# MOTOR_DRIVER_dupl.net
KiCad netlist of a schematic drawn in EAGLE
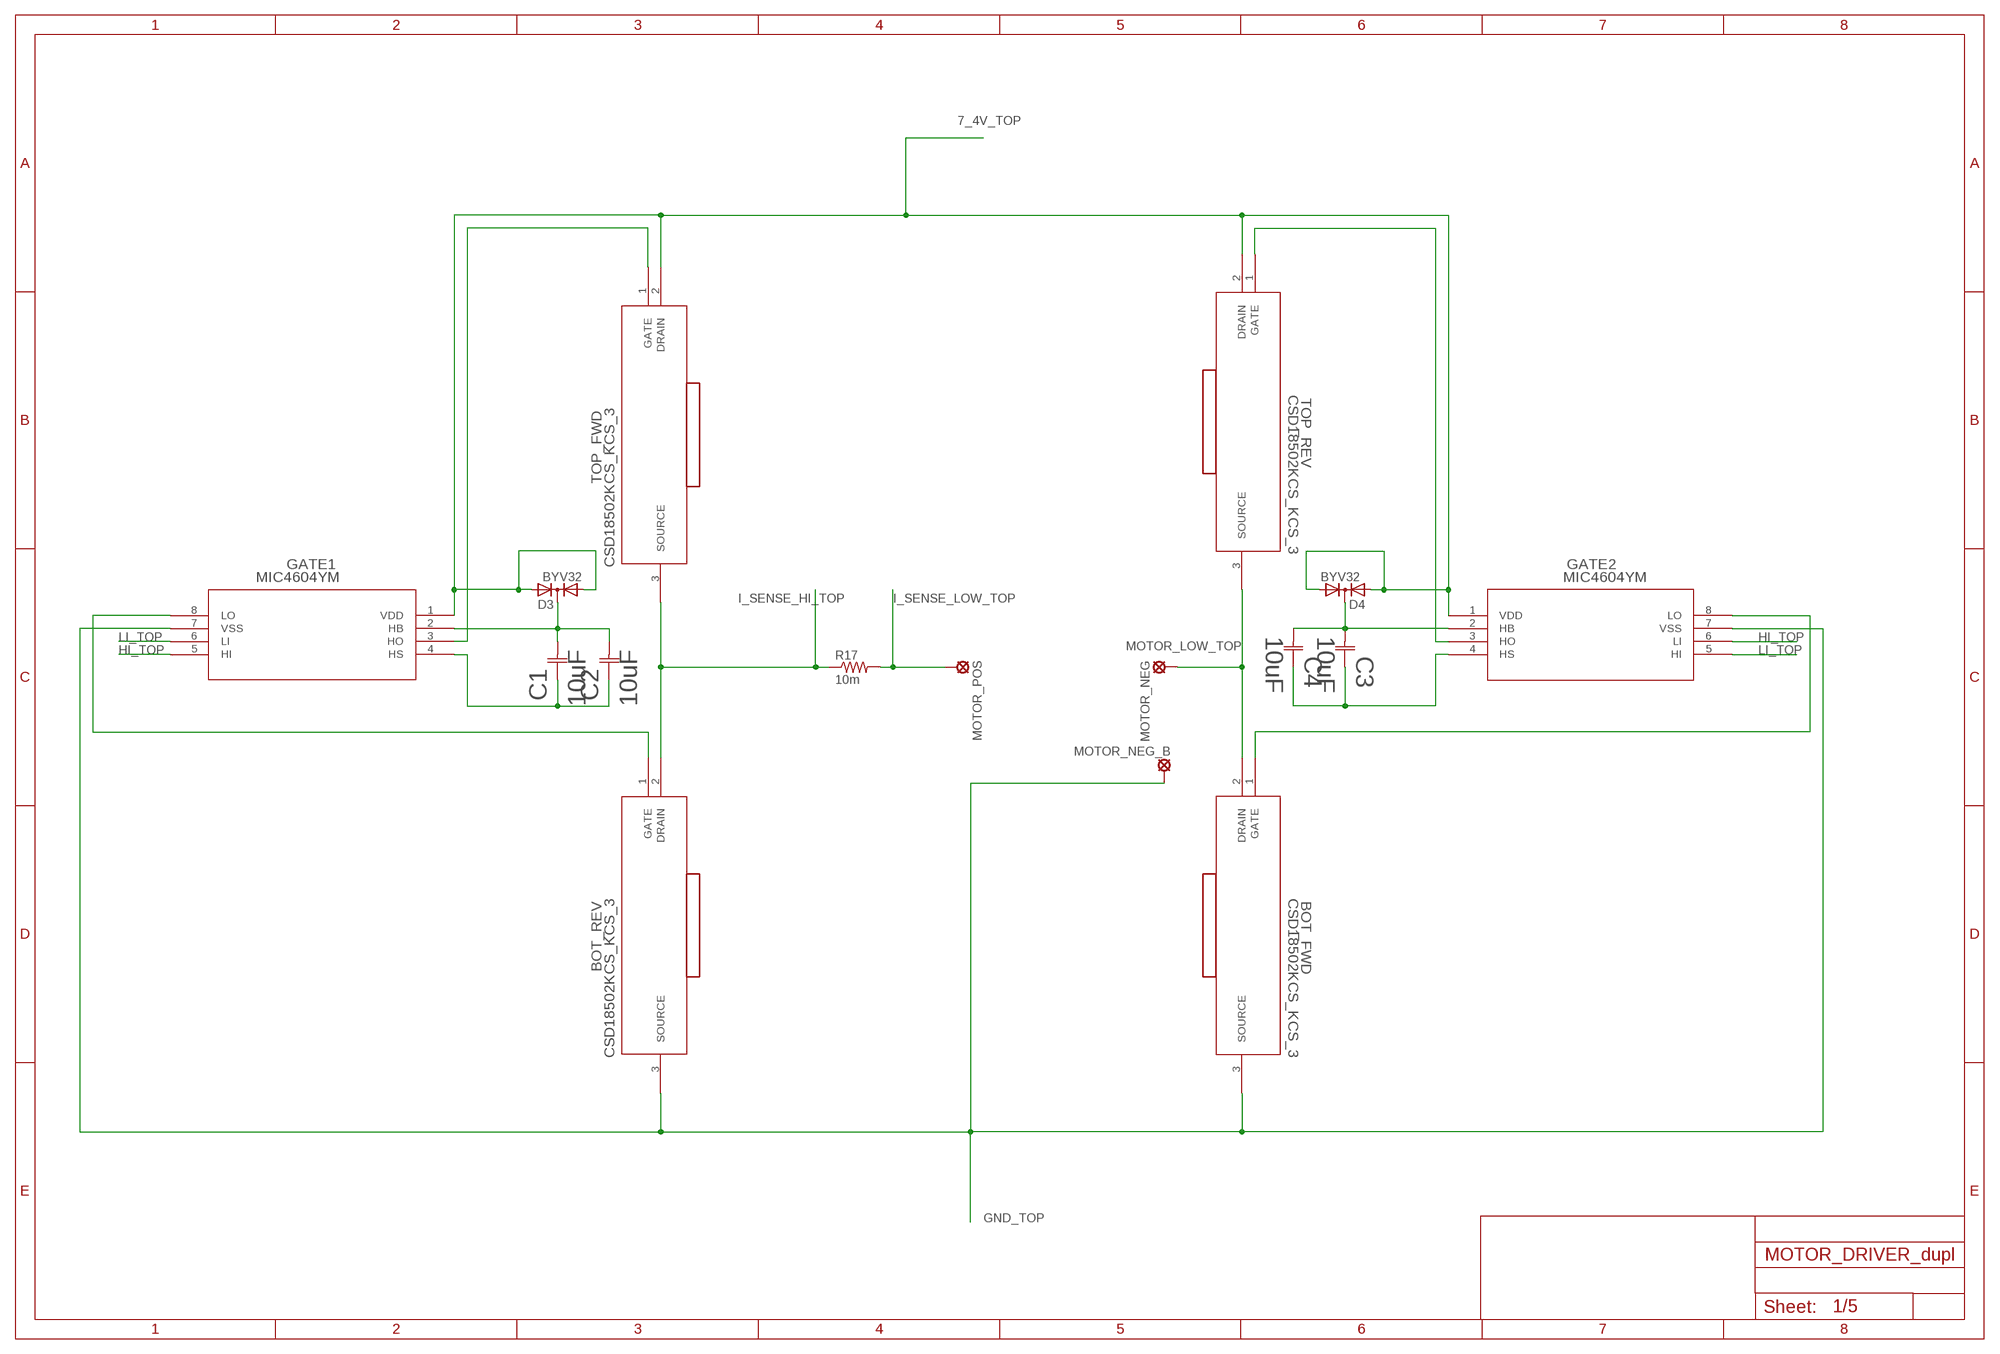
[diagram p0: schematic, sheet 1]
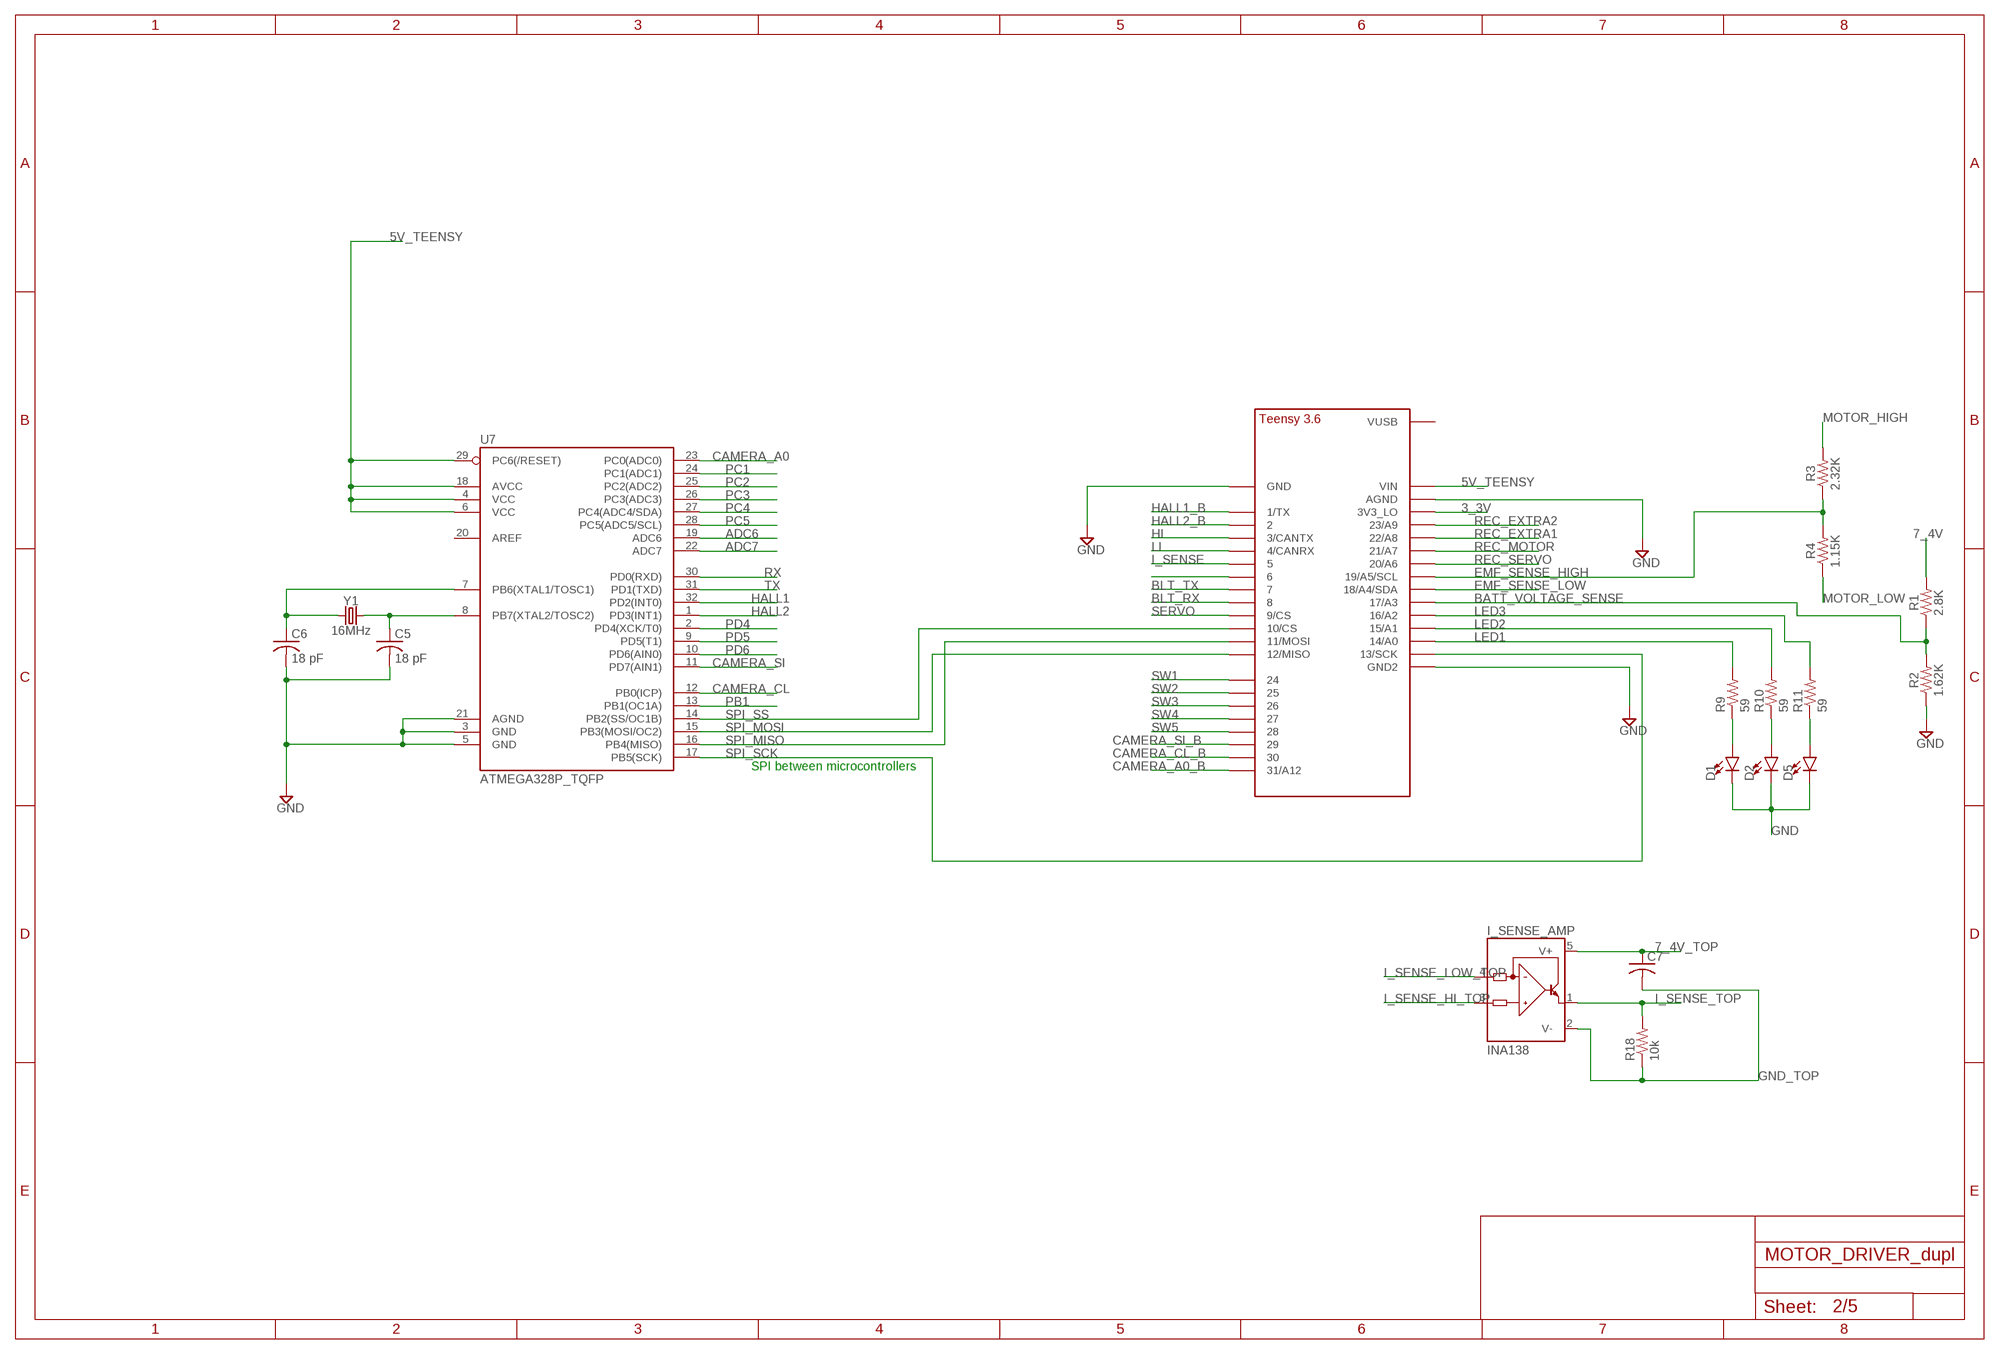
[diagram p1: schematic, sheet 2]
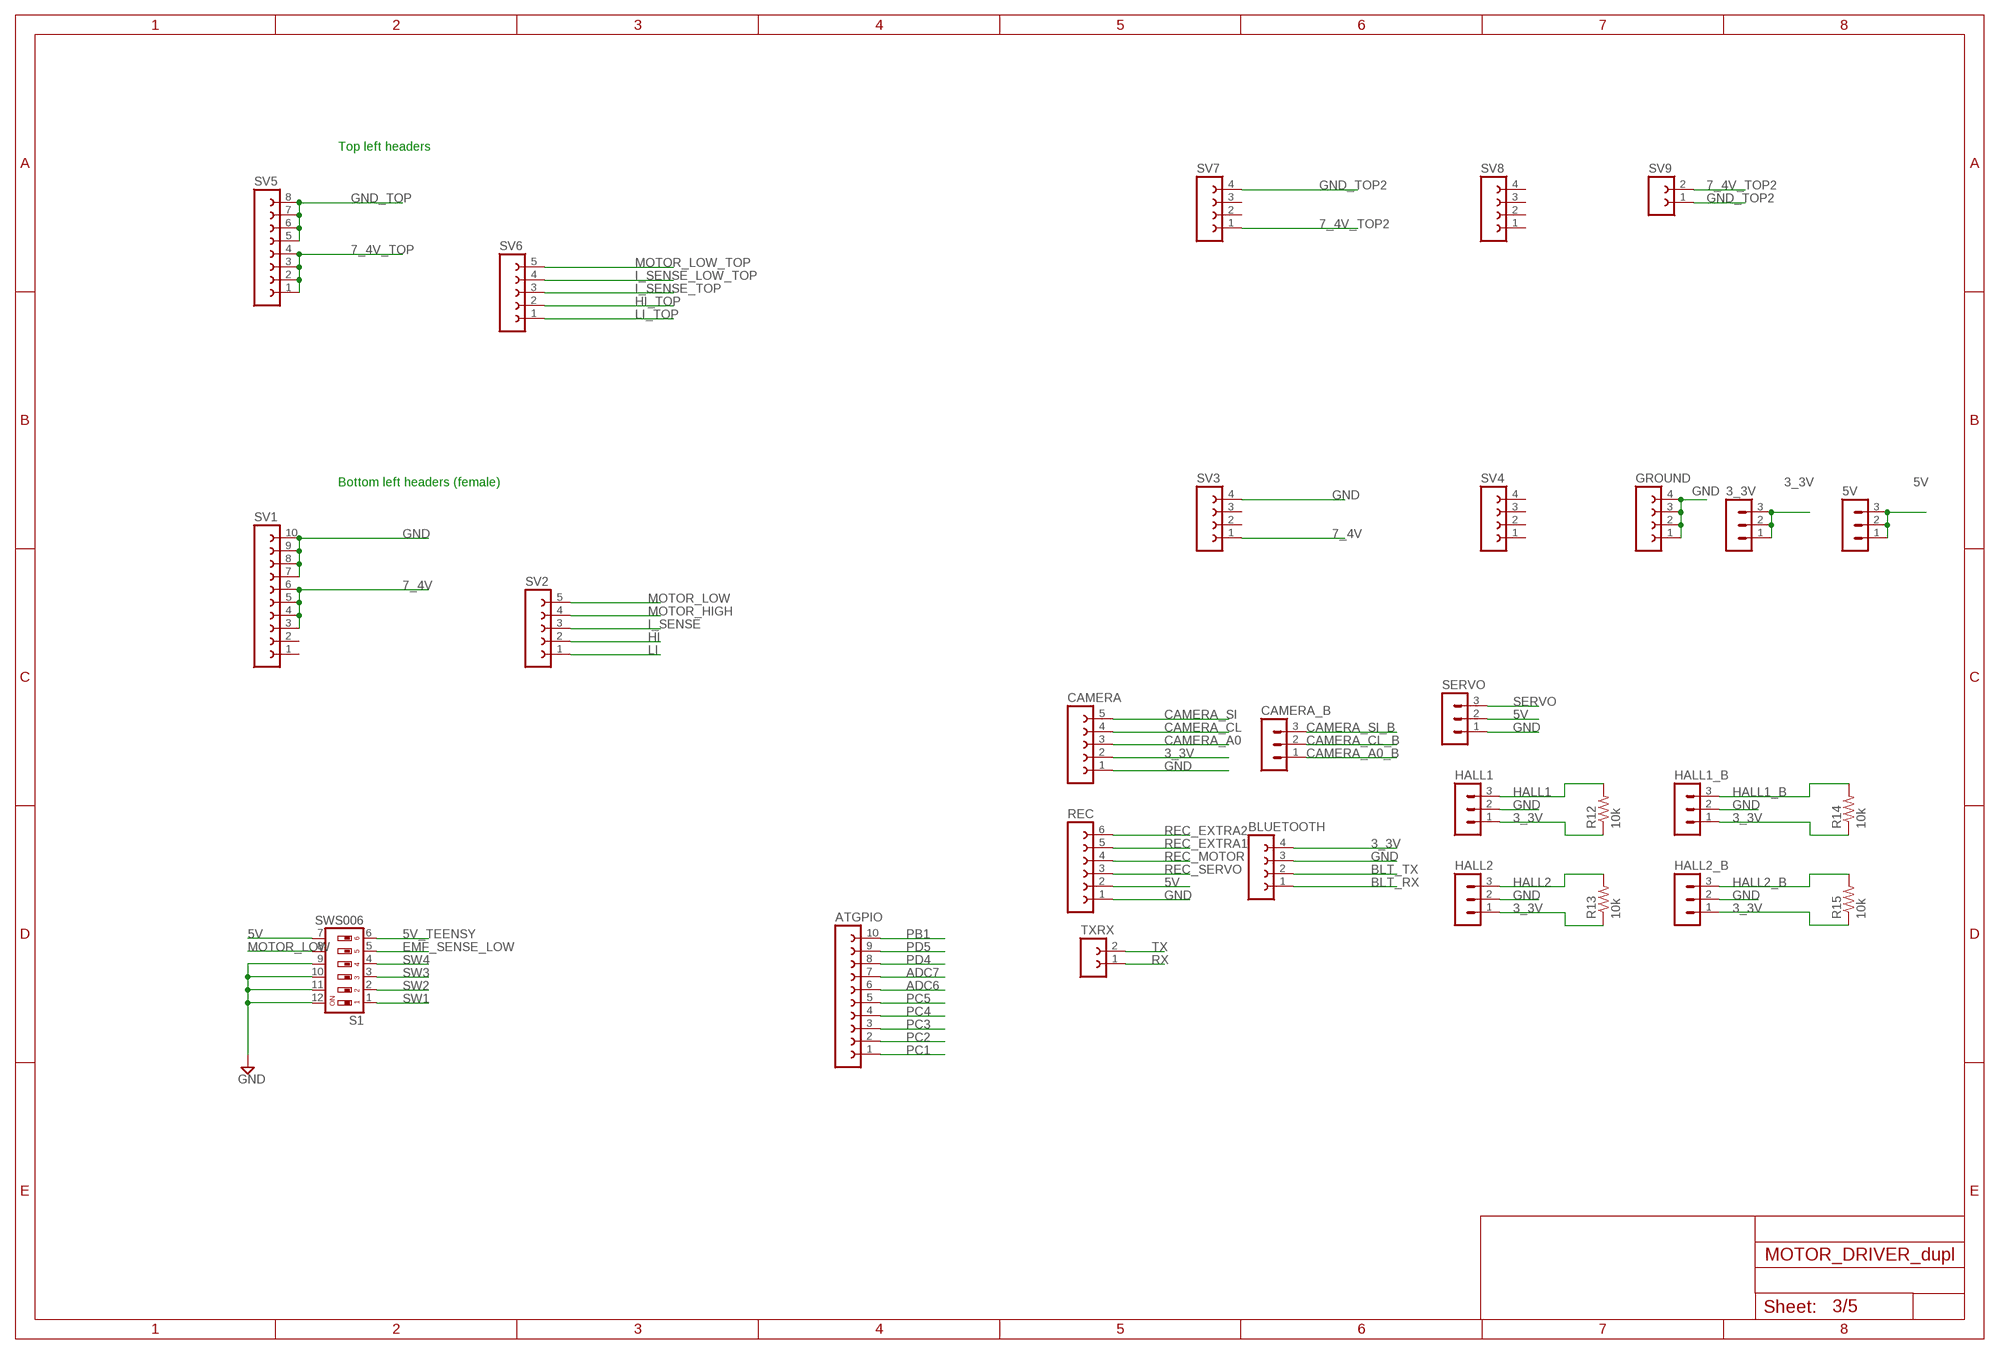
[diagram p2: schematic, sheet 3]
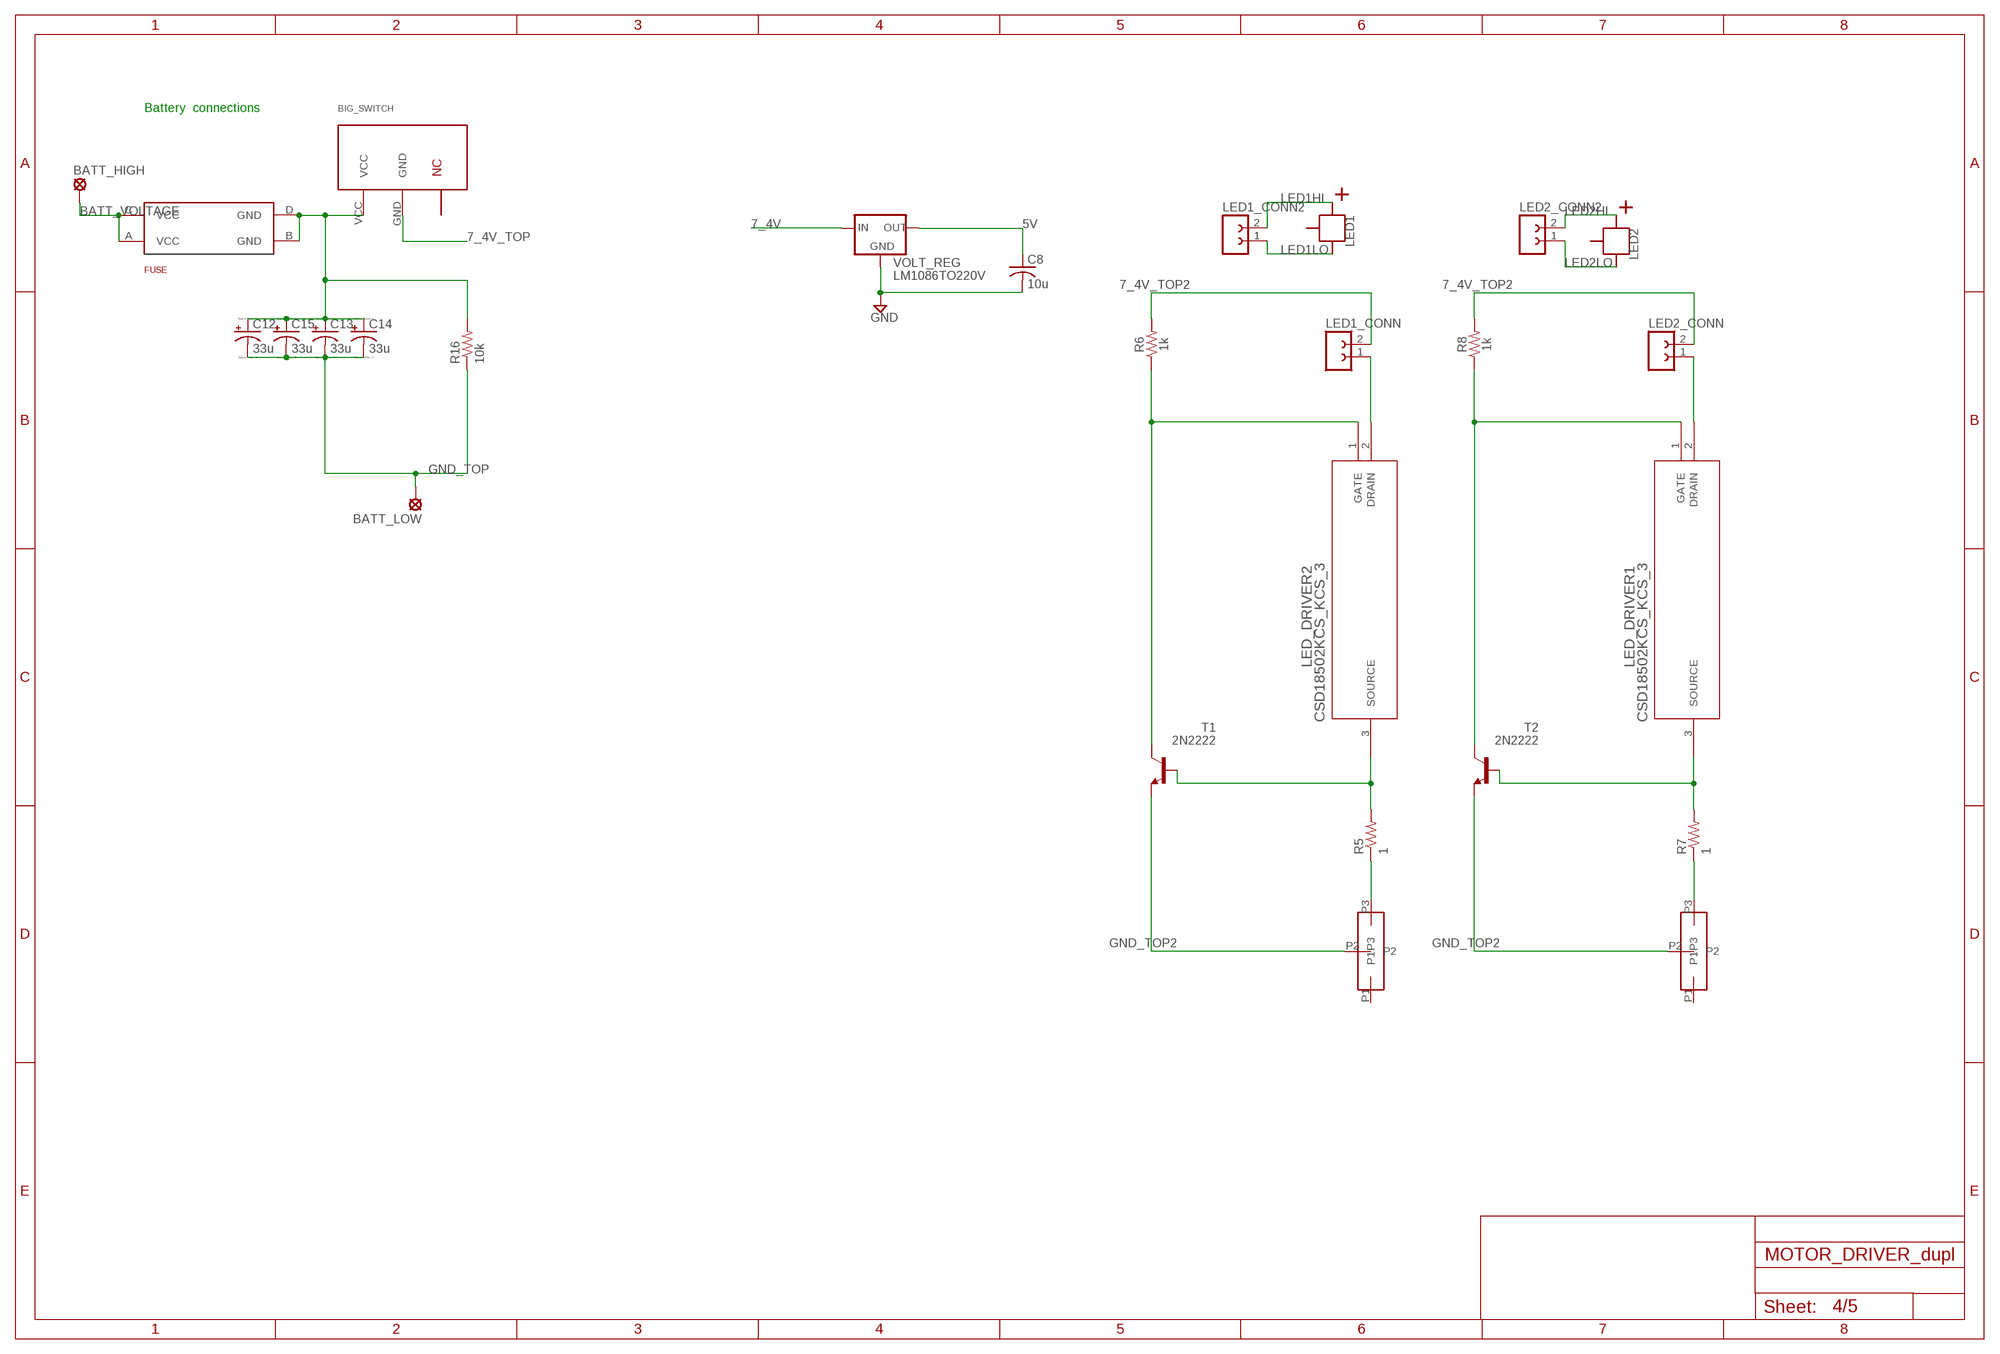
[diagram p3: schematic, sheet 4]
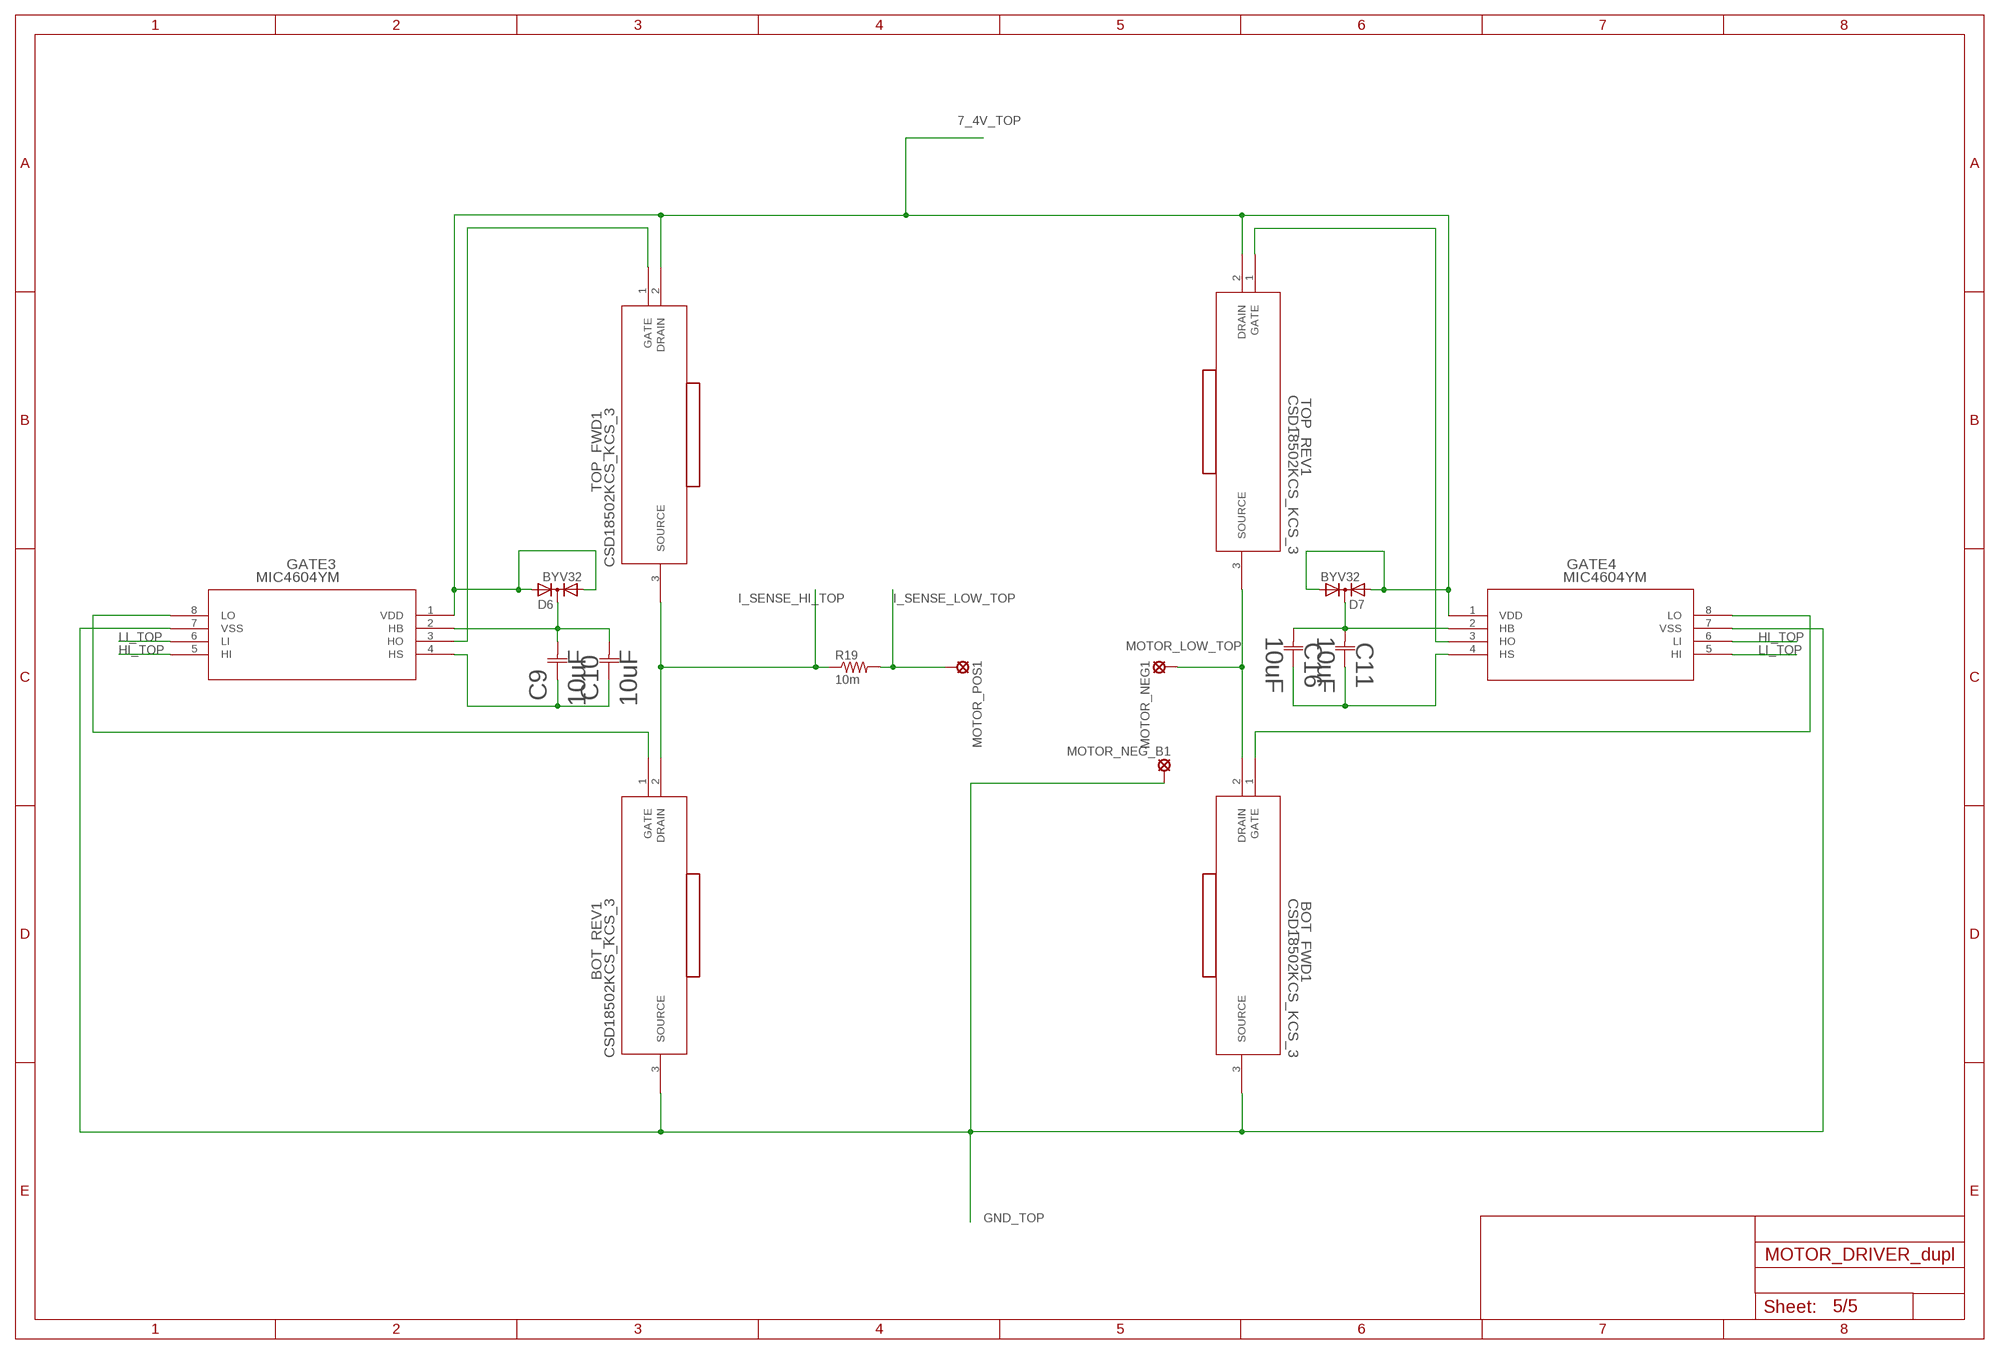
[diagram p4: schematic, sheet 5]

(export (version "E")
  (design (tool "Eeschema 10.0.6"))
  (components
    (comp (ref "C5")
      (value "18 pF")
      (footprint "eagle-import:C0603")
      (libsource (lib "eagle-import") (part "C-USC0603"))
    )
    (comp (ref "C6")
      (value "18 pF")
      (footprint "eagle-import:C0603")
      (libsource (lib "eagle-import") (part "C-USC0603"))
    )
    (comp (ref "C7")
      (value "C-USC0603")
      (footprint "eagle-import:C0603")
      (libsource (lib "eagle-import") (part "resistor_C-USC0603"))
    )
    (comp (ref "D1")
      (value "LED0603")
      (footprint "eagle-import:LED-0603")
      (libsource (lib "eagle-import") (part "LED0603"))
    )
    (comp (ref "D2")
      (value "LED0603")
      (footprint "eagle-import:LED-0603")
      (libsource (lib "eagle-import") (part "LED0603"))
    )
    (comp (ref "D5")
      (value "LED0603")
      (footprint "eagle-import:LED-0603")
      (libsource (lib "eagle-import") (part "LED0603"))
    )
    (comp (ref "I_SENSE_AMP")
      (value "INA138")
      (footprint "eagle-import:SOT23-5")
      (fields
        (field (name "DIGIKEY_PART_NUMBER") "INA138NACT-ND")
        (field (name "MANUFACTURER") "Texas Instruments")
        (field (name "MANUFACTURER_PART_NUMBER") "INA138NA/250")
      )
      (libsource (lib "eagle-import") (part "INA138"))
    )
    (comp (ref "R1")
      (value "2.8K")
      (footprint "eagle-import:0805")
      (fields
        (field (name "DIGIKEY_PART_NUMBER") "311-2.80KCRCT-ND")
        (field (name "MANUFACTURER") "Yageo")
        (field (name "MANUFACTURER_PART_NUMBER") "RC0805FR-072K8L")
      )
      (libsource (lib "eagle-import") (part "0.3OHM-0805-1/8W-1%"))
    )
    (comp (ref "R2")
      (value "1.62K")
      (footprint "eagle-import:0805")
      (fields
        (field (name "DIGIKEY_PART_NUMBER") "311-1.62KCRCT-ND")
        (field (name "MANUFACTURER") "Yageo")
        (field (name "MANUFACTURER_PART_NUMBER") "RC0805FR-071K62L")
      )
      (libsource (lib "eagle-import") (part "0.3OHM-0805-1/8W-1%"))
    )
    (comp (ref "R3")
      (value "2.32K")
      (footprint "eagle-import:0805")
      (fields
        (field (name "DIGIKEY_PART_NUMBER") "311-2.32KCRCT-ND")
        (field (name "MANUFACTURER") "Yageo")
        (field (name "MANUFACTURER_PART_NUMBER") "RC0805FR-072K32L")
      )
      (libsource (lib "eagle-import") (part "0.3OHM-0805-1/8W-1%"))
    )
    (comp (ref "R4")
      (value "1.15K")
      (footprint "eagle-import:0805")
      (fields
        (field (name "DIGIKEY_PART_NUMBER") "311-1.15KCRCT-ND")
        (field (name "MANUFACTURER") "Yageo")
        (field (name "MANUFACTURER_PART_NUMBER") "RC0805FR-071K15L")
      )
      (libsource (lib "eagle-import") (part "0.3OHM-0805-1/8W-1%"))
    )
    (comp (ref "R9")
      (value "59")
      (footprint "eagle-import:R0805")
      (libsource (lib "eagle-import") (part "R-US_R0805"))
    )
    (comp (ref "R10")
      (value "59")
      (footprint "eagle-import:R0805")
      (libsource (lib "eagle-import") (part "R-US_R0805"))
    )
    (comp (ref "R11")
      (value "59")
      (footprint "eagle-import:R0805")
      (libsource (lib "eagle-import") (part "R-US_R0805"))
    )
    (comp (ref "R18")
      (value "10k")
      (footprint "eagle-import:R0603")
      (libsource (lib "eagle-import") (part "R-US_R0603"))
    )
    (comp (ref "U$1")
      (value "TEENSY_3.5/3.6_FEWER")
      (footprint "eagle-import:TEENSY_3.5_3.6_BASIC_FEWER_PIN")
      (fields
        (field (name "DIGIKEY_PART_NUMBER") "1568-1443-ND")
        (field (name "MANUFACTURER") "SparkFun Electronics")
        (field (name "MANUFACTURER_PART_NUMBER") "DEV-14055")
      )
      (libsource (lib "eagle-import") (part "TEENSY_3.5/3.6_FEWER"))
    )
    (comp (ref "U7")
      (value "ATMEGA328P_TQFP")
      (footprint "eagle-import:TQFP32-08")
      (fields
        (field (name "DIGIKEY_PART_NUMBER") "ATMEGA328PB-AU-ND")
        (field (name "MANUFACTURER") "Microchip Technology")
        (field (name "MANUFACTURER_PART_NUMBER") "ATMEGA328PB-AU")
      )
      (libsource (lib "eagle-import") (part "ATMEGA328P_TQFP"))
    )
    (comp (ref "Y1")
      (value "16MHz")
      (footprint "eagle-import:HC49US")
      (fields
        (field (name "DIGIKEY_PART_NUMBER") "887-2425-1-ND")
        (field (name "MANUFACTURER") "TXC CORPORATION")
        (field (name "MANUFACTURER_PART_NUMBER") "9C-16.000MBBK-T")
      )
      (libsource (lib "eagle-import") (part "CRYSTAL-16MHZPTH-HC49US"))
    )
    (comp (ref "3_3V")
      (value "MA03-1")
      (footprint "eagle-import:MA03-1")
      (libsource (lib "eagle-import") (part "MA03-1"))
    )
    (comp (ref "5V")
      (value "MA03-1")
      (footprint "eagle-import:MA03-1")
      (libsource (lib "eagle-import") (part "MA03-1"))
    )
    (comp (ref "ATGPIO")
      (value "FE10-1")
      (footprint "eagle-import:FE10")
      (libsource (lib "eagle-import") (part "FE10-1"))
    )
    (comp (ref "BLUETOOTH")
      (value "FE04-1")
      (footprint "eagle-import:FE04-1")
      (fields
        (field (name "MANUFACTURER") "HC Information Technology")
        (field (name "MANUFACTURER_PART_NUMBER") "HC-06")
      )
      (libsource (lib "eagle-import") (part "FE04-1"))
    )
    (comp (ref "CAMERA")
      (value "FE05-1")
      (footprint "eagle-import:FE05-1")
      (fields
        (field (name "DIGIKEY_PART_NUMBER") "28317-ND")
        (field (name "MANUFACTURER") "Parallax")
        (field (name "MANUFACTURER_PART_NUMBER") "28317")
      )
      (libsource (lib "eagle-import") (part "FE05-1"))
    )
    (comp (ref "CAMERA_B")
      (value "MA03-1")
      (footprint "eagle-import:MA03-1")
      (fields
        (field (name "DIGIKEY_PART_NUMBER") "28317-ND")
        (field (name "MANUFACTURER") "Parallax")
        (field (name "MANUFACTURER_PART_NUMBER") "28317")
      )
      (libsource (lib "eagle-import") (part "MA03-1"))
    )
    (comp (ref "GROUND")
      (value "FE04-1")
      (footprint "eagle-import:FE04-1")
      (libsource (lib "eagle-import") (part "FE04-1"))
    )
    (comp (ref "HALL1")
      (value "MA03-1")
      (footprint "eagle-import:MA03-1")
      (fields
        (field (name "DIGIKEY_PART_NUMBER") "US1881LUA-AAA-000-BU-ND")
        (field (name "MANUFACTURER") "Melexis Technologies NV")
        (field (name "MANUFACTURER_PART_NUMBER") "US1881LUA-AAA-000-BU")
      )
      (libsource (lib "eagle-import") (part "MA03-1"))
    )
    (comp (ref "HALL1_B")
      (value "MA03-1")
      (footprint "eagle-import:MA03-1")
      (fields
        (field (name "DIGIKEY_PART_NUMBER") "US1881LUA-AAA-000-BU-ND")
        (field (name "MANUFACTURER") "Melexis Technologies NV")
        (field (name "MANUFACTURER_PART_NUMBER") "US1881LUA-AAA-000-BU")
      )
      (libsource (lib "eagle-import") (part "MA03-1"))
    )
    (comp (ref "HALL2")
      (value "MA03-1")
      (footprint "eagle-import:MA03-1")
      (fields
        (field (name "DIGIKEY_PART_NUMBER") "US1881LUA-AAA-000-BU-ND")
        (field (name "MANUFACTURER") "Melexis Technologies NV")
        (field (name "MANUFACTURER_PART_NUMBER") "US1881LUA-AAA-000-BU")
      )
      (libsource (lib "eagle-import") (part "MA03-1"))
    )
    (comp (ref "HALL2_B")
      (value "MA03-1")
      (footprint "eagle-import:MA03-1")
      (fields
        (field (name "DIGIKEY_PART_NUMBER") "US1881LUA-AAA-000-BU-ND")
        (field (name "MANUFACTURER") "Melexis Technologies NV")
        (field (name "MANUFACTURER_PART_NUMBER") "US1881LUA-AAA-000-BU")
      )
      (libsource (lib "eagle-import") (part "MA03-1"))
    )
    (comp (ref "R12")
      (value "10k")
      (footprint "eagle-import:R0603")
      (libsource (lib "eagle-import") (part "resistor_R-US_R0603"))
    )
    (comp (ref "R13")
      (value "10k")
      (footprint "eagle-import:R0603")
      (libsource (lib "eagle-import") (part "resistor_R-US_R0603"))
    )
    (comp (ref "R14")
      (value "10k")
      (footprint "eagle-import:R0603")
      (libsource (lib "eagle-import") (part "resistor_R-US_R0603"))
    )
    (comp (ref "R15")
      (value "10k")
      (footprint "eagle-import:R0603")
      (libsource (lib "eagle-import") (part "resistor_R-US_R0603"))
    )
    (comp (ref "REC")
      (value "FE06-1")
      (footprint "eagle-import:FE06")
      (libsource (lib "eagle-import") (part "FE06-1"))
    )
    (comp (ref "S1")
      (value "SWS006")
      (footprint "eagle-import:SMS-006")
      (fields
        (field (name "DIGIKEY_PART_NUMBER") "CT2196MST-ND")
        (field (name "MANUFACTURER") "CTS Electrocomponents")
        (field (name "MANUFACTURER_PART_NUMBER") "219-6MST")
      )
      (libsource (lib "eagle-import") (part "SWS006"))
    )
    (comp (ref "SERVO")
      (value "MA03-1")
      (footprint "eagle-import:MA03-1")
      (fields (field (name "MANUFACTURER") "TrackStar") (field (name "MANUFACTURER_PART_NUMBER") "TS-P12S"))
      (libsource (lib "eagle-import") (part "MA03-1"))
    )
    (comp (ref "SV1")
      (value "FE10-1")
      (footprint "eagle-import:FE10")
      (libsource (lib "eagle-import") (part "FE10-1"))
    )
    (comp (ref "SV2")
      (value "FE05-1")
      (footprint "eagle-import:FE05-1")
      (libsource (lib "eagle-import") (part "FE05-1"))
    )
    (comp (ref "SV3")
      (value "FE04-1")
      (footprint "eagle-import:FE04-1")
      (libsource (lib "eagle-import") (part "FE04-1"))
    )
    (comp (ref "SV4")
      (value "FE04-1")
      (footprint "eagle-import:FE04-1")
      (libsource (lib "eagle-import") (part "FE04-1"))
    )
    (comp (ref "SV5")
      (value "FE08-1")
      (footprint "eagle-import:FE08")
      (libsource (lib "eagle-import") (part "FE08-1"))
    )
    (comp (ref "SV6")
      (value "FE05-1")
      (footprint "eagle-import:FE05-1")
      (libsource (lib "eagle-import") (part "FE05-1"))
    )
    (comp (ref "SV7")
      (value "FE04-1")
      (footprint "eagle-import:FE04-1")
      (libsource (lib "eagle-import") (part "FE04-1"))
    )
    (comp (ref "SV8")
      (value "FE04-1")
      (footprint "eagle-import:FE04-1")
      (libsource (lib "eagle-import") (part "FE04-1"))
    )
    (comp (ref "SV9")
      (value "FE02-1")
      (footprint "eagle-import:FE02-1")
      (libsource (lib "eagle-import") (part "FE02-1"))
    )
    (comp (ref "TXRX")
      (value "FE02-1")
      (footprint "eagle-import:FE02-1")
      (libsource (lib "eagle-import") (part "FE02-1"))
    )
    (comp (ref "BOT_FWD")
      (value "CSD18502KCS_KCS_3")
      (footprint "eagle-import:KCS3")
      (fields
        (field (name "DIGIKEY_PART_NUMBER") "296-35013-ND")
        (field (name "MANUFACTURER") "Texas Instruments")
        (field (name "MANUFACTURER_PART_NUMBER") "CSD18533KCS")
      )
      (libsource (lib "eagle-import") (part "CSD18502KCS_KCS_3"))
    )
    (comp (ref "BOT_REV")
      (value "CSD18502KCS_KCS_3")
      (footprint "eagle-import:KCS3")
      (fields
        (field (name "DIGIKEY_PART_NUMBER") "296-35013-ND")
        (field (name "MANUFACTURER") "Texas Instruments")
        (field (name "MANUFACTURER_PART_NUMBER") "CSD18533KCS")
      )
      (libsource (lib "eagle-import") (part "CSD18502KCS_KCS_3"))
    )
    (comp (ref "C1")
      (value "10uF")
      (footprint "eagle-import:CAP_EEE_B")
      (fields (field (name "MANUFACTURER_PART_NUMBER") "EEE1VA100WR"))
      (libsource (lib "eagle-import") (part "EEE1VA100WR"))
    )
    (comp (ref "C2")
      (value "10uF")
      (footprint "eagle-import:CAP_EEE_B")
      (fields (field (name "MANUFACTURER_PART_NUMBER") "EEE1VA100WR"))
      (libsource (lib "eagle-import") (part "EEE1VA100WR"))
    )
    (comp (ref "C3")
      (value "10uF")
      (footprint "eagle-import:CAP_EEE_B")
      (fields (field (name "MANUFACTURER_PART_NUMBER") "EEE1VA100WR"))
      (libsource (lib "eagle-import") (part "EEE1VA100WR"))
    )
    (comp (ref "C4")
      (value "10uF")
      (footprint "eagle-import:CAP_EEE_B")
      (fields (field (name "MANUFACTURER_PART_NUMBER") "EEE1VA100WR"))
      (libsource (lib "eagle-import") (part "EEE1VA100WR"))
    )
    (comp (ref "D3")
      (value "BYV32")
      (footprint "eagle-import:TO220ABS")
      (libsource (lib "eagle-import") (part "BYV32"))
    )
    (comp (ref "D4")
      (value "BYV32")
      (footprint "eagle-import:TO220ABS")
      (libsource (lib "eagle-import") (part "BYV32"))
    )
    (comp (ref "GATE1")
      (value "MIC4604YM")
      (footprint "eagle-import:SOIC-8_M")
      (fields
        (field (name "DIGIKEY_PART_NUMBER") "576-4395-1-ND")
        (field (name "MANUFACTURER") "Microchip")
        (field (name "MANUFACTURER_PART_NUMBER") "MIC4604YM-T5")
      )
      (libsource (lib "eagle-import") (part "MIC4604YM"))
    )
    (comp (ref "GATE2")
      (value "MIC4604YM")
      (footprint "eagle-import:SOIC-8_M")
      (fields
        (field (name "DIGIKEY_PART_NUMBER") "576-4395-1-ND")
        (field (name "MANUFACTURER") "Microchip")
        (field (name "MANUFACTURER_PART_NUMBER") "MIC4604YM-T5")
      )
      (libsource (lib "eagle-import") (part "MIC4604YM"))
    )
    (comp (ref "MOTOR_NEG")
      (value "SE14")
      (footprint "eagle-import:SE14")
      (libsource (lib "eagle-import") (part "SE14"))
    )
    (comp (ref "MOTOR_NEG_B")
      (value "SE14")
      (footprint "eagle-import:SE14")
      (libsource (lib "eagle-import") (part "SE14"))
    )
    (comp (ref "MOTOR_POS")
      (value "SE14")
      (footprint "eagle-import:SE14")
      (libsource (lib "eagle-import") (part "SE14"))
    )
    (comp (ref "R17")
      (value "10m")
      (footprint "eagle-import:R2512")
      (libsource (lib "eagle-import") (part "R-US_R2512"))
    )
    (comp (ref "TOP_FWD")
      (value "CSD18502KCS_KCS_3")
      (footprint "eagle-import:KCS3")
      (fields
        (field (name "DIGIKEY_PART_NUMBER") "296-35013-ND")
        (field (name "MANUFACTURER") "Texas Instruments")
        (field (name "MANUFACTURER_PART_NUMBER") "CSD18533KCS")
      )
      (libsource (lib "eagle-import") (part "CSD18502KCS_KCS_3"))
    )
    (comp (ref "TOP_REV")
      (value "CSD18502KCS_KCS_3")
      (footprint "eagle-import:KCS3")
      (fields
        (field (name "DIGIKEY_PART_NUMBER") "296-35013-ND")
        (field (name "MANUFACTURER") "Texas Instruments")
        (field (name "MANUFACTURER_PART_NUMBER") "CSD18533KCS")
      )
      (libsource (lib "eagle-import") (part "CSD18502KCS_KCS_3"))
    )
    (comp (ref "U$2")
      (value "HEATSINK")
      (footprint "eagle-import:HEATSINK")
      (fields
        (field (name "DIGIKEY_PART_NUMBER") "HS112-ND")
        (field (name "MANUFACTURER") "Aavid Thermalloy")
        (field (name "MANUFACTURER_PART_NUMBER") "507002B00000G")
      )
      (libsource (lib "eagle-import") (part "HEATSINK"))
    )
    (comp (ref "U$4")
      (value "HEATSINK")
      (footprint "eagle-import:HEATSINK")
      (fields
        (field (name "DIGIKEY_PART_NUMBER") "HS112-ND")
        (field (name "MANUFACTURER") "Aavid Thermalloy")
        (field (name "MANUFACTURER_PART_NUMBER") "507002B00000G")
      )
      (libsource (lib "eagle-import") (part "HEATSINK"))
    )
    (comp (ref "U$5")
      (value "HEATSINK")
      (footprint "eagle-import:HEATSINK")
      (fields
        (field (name "DIGIKEY_PART_NUMBER") "HS112-ND")
        (field (name "MANUFACTURER") "Aavid Thermalloy")
        (field (name "MANUFACTURER_PART_NUMBER") "507002B00000G")
      )
      (libsource (lib "eagle-import") (part "HEATSINK"))
    )
    (comp (ref "U$6")
      (value "HEATSINK")
      (footprint "eagle-import:HEATSINK")
      (fields
        (field (name "DIGIKEY_PART_NUMBER") "HS112-ND")
        (field (name "MANUFACTURER") "Aavid Thermalloy")
        (field (name "MANUFACTURER_PART_NUMBER") "507002B00000G")
      )
      (libsource (lib "eagle-import") (part "HEATSINK"))
    )
    (comp (ref "BATT_HIGH")
      (value "SE14")
      (footprint "eagle-import:SE14")
      (libsource (lib "eagle-import") (part "SE14"))
    )
    (comp (ref "BATT_LOW")
      (value "SE14")
      (footprint "eagle-import:SE14")
      (libsource (lib "eagle-import") (part "SE14"))
    )
    (comp (ref "BIG_SWITCH")
      (value "BIGSWITCH")
      (footprint "eagle-import:BIGSWITCH")
      (fields
        (field (name "DIGIKEY_PART_NUMBER") "CW106-ND")
        (field (name "MANUFACTURER") "CW Industries")
        (field (name "MANUFACTURER_PART_NUMBER") "GRB238B801BR1")
      )
      (libsource (lib "eagle-import") (part "BIGSWITCH"))
    )
    (comp (ref "C8")
      (value "10u")
      (footprint "eagle-import:C0805")
      (libsource (lib "eagle-import") (part "C-USC0805"))
    )
    (comp (ref "C12")
      (value "33u")
      (footprint "eagle-import:153CLV-1010")
      (libsource (lib "eagle-import") (part "CPOL-US153CLV-1010"))
    )
    (comp (ref "C13")
      (value "33u")
      (footprint "eagle-import:153CLV-1010")
      (libsource (lib "eagle-import") (part "CPOL-US153CLV-1010"))
    )
    (comp (ref "C14")
      (value "33u")
      (footprint "eagle-import:153CLV-1010")
      (libsource (lib "eagle-import") (part "CPOL-US153CLV-1010"))
    )
    (comp (ref "C15")
      (value "33u")
      (footprint "eagle-import:153CLV-1010")
      (libsource (lib "eagle-import") (part "CPOL-US153CLV-1010"))
    )
    (comp (ref "FUSE")
      (value "FUSEHOLDER3588")
      (footprint "eagle-import:FUSEHOLDER3588")
      (fields
        (field (name "DIGIKEY_PART_NUMBER") "F4989-ND")
        (field (name "MANUFACTURER") "Littelfuse Inc.")
        (field (name "MANUFACTURER_PART_NUMBER") "0891010.NXS")
      )
      (libsource (lib "eagle-import") (part "FUSEHOLDER3588"))
    )
    (comp (ref "LED1")
      (value "CREE_XP")
      (footprint "eagle-import:XP")
      (libsource (lib "eagle-import") (part "CREE_XP"))
    )
    (comp (ref "LED1_CONN")
      (value "FE02-1")
      (footprint "eagle-import:FE02-1")
      (libsource (lib "eagle-import") (part "FE02-1"))
    )
    (comp (ref "LED1_CONN2")
      (value "FE02-1")
      (footprint "eagle-import:FE02-1")
      (libsource (lib "eagle-import") (part "FE02-1"))
    )
    (comp (ref "LED2")
      (value "CREE_XP")
      (footprint "eagle-import:XP")
      (libsource (lib "eagle-import") (part "CREE_XP"))
    )
    (comp (ref "LED2_CONN")
      (value "FE02-1")
      (footprint "eagle-import:FE02-1")
      (libsource (lib "eagle-import") (part "FE02-1"))
    )
    (comp (ref "LED2_CONN2")
      (value "FE02-1")
      (footprint "eagle-import:FE02-1")
      (libsource (lib "eagle-import") (part "FE02-1"))
    )
    (comp (ref "LED_DRIVER1")
      (value "CSD18502KCS_KCS_3")
      (footprint "eagle-import:KCS3")
      (fields
        (field (name "DIGIKEY_PART_NUMBER") "296-35013-ND")
        (field (name "MANUFACTURER") "Texas Instruments")
        (field (name "MANUFACTURER_PART_NUMBER") "CSD18533KCS")
      )
      (libsource (lib "eagle-import") (part "CSD18502KCS_KCS_3"))
    )
    (comp (ref "LED_DRIVER2")
      (value "CSD18502KCS_KCS_3")
      (footprint "eagle-import:KCS3")
      (fields
        (field (name "DIGIKEY_PART_NUMBER") "296-35013-ND")
        (field (name "MANUFACTURER") "Texas Instruments")
        (field (name "MANUFACTURER_PART_NUMBER") "CSD18533KCS")
      )
      (libsource (lib "eagle-import") (part "CSD18502KCS_KCS_3"))
    )
    (comp (ref "R5")
      (value "1")
      (footprint "eagle-import:R2512")
      (libsource (lib "eagle-import") (part "R-US_R2512"))
    )
    (comp (ref "R6")
      (value "1k")
      (footprint "eagle-import:AXIAL-0.3")
      (libsource (lib "eagle-import") (part "1KOHM-HORIZ-1/4W-1%"))
    )
    (comp (ref "R7")
      (value "1")
      (footprint "eagle-import:R2512")
      (libsource (lib "eagle-import") (part "R-US_R2512"))
    )
    (comp (ref "R8")
      (value "1k")
      (footprint "eagle-import:AXIAL-0.3")
      (libsource (lib "eagle-import") (part "1KOHM-HORIZ-1/4W-1%"))
    )
    (comp (ref "R16")
      (value "10k")
      (footprint "eagle-import:R0603")
      (libsource (lib "eagle-import") (part "resistor_R-US_R0603"))
    )
    (comp (ref "T1")
      (value "2N2222")
      (footprint "eagle-import:TO18")
      (libsource (lib "eagle-import") (part "2N2222"))
    )
    (comp (ref "T2")
      (value "2N2222")
      (footprint "eagle-import:TO18")
      (libsource (lib "eagle-import") (part "2N2222"))
    )
    (comp (ref "U$3")
      (value "POT")
      (footprint "eagle-import:POT")
      (libsource (lib "eagle-import") (part "POT"))
    )
    (comp (ref "U$7")
      (value "POT")
      (footprint "eagle-import:POT")
      (libsource (lib "eagle-import") (part "POT"))
    )
    (comp (ref "VOLT_REG")
      (value "LM1086TO220V")
      (footprint "eagle-import:TO220S")
      (fields
        (field (name "DIGIKEY_PART_NUMBER") "LM1086IT-5.0/NOPB-ND")
        (field (name "MANUFACTURER") "Texas Instruments")
        (field (name "MANUFACTURER_PART_NUMBER") "LM1086IT-5.0/NOPB")
      )
      (libsource (lib "eagle-import") (part "LM1086TO220V"))
    )
    (comp (ref "BOT_FWD1")
      (value "CSD18502KCS_KCS_3")
      (footprint "eagle-import:KCS3")
      (fields
        (field (name "DIGIKEY_PART_NUMBER") "296-35013-ND")
        (field (name "MANUFACTURER") "Texas Instruments")
        (field (name "MANUFACTURER_PART_NUMBER") "CSD18533KCS")
      )
      (libsource (lib "eagle-import") (part "CSD18502KCS_KCS_3"))
    )
    (comp (ref "BOT_REV1")
      (value "CSD18502KCS_KCS_3")
      (footprint "eagle-import:KCS3")
      (fields
        (field (name "DIGIKEY_PART_NUMBER") "296-35013-ND")
        (field (name "MANUFACTURER") "Texas Instruments")
        (field (name "MANUFACTURER_PART_NUMBER") "CSD18533KCS")
      )
      (libsource (lib "eagle-import") (part "CSD18502KCS_KCS_3"))
    )
    (comp (ref "C9")
      (value "10uF")
      (footprint "eagle-import:CAP_EEE_B")
      (fields (field (name "MANUFACTURER_PART_NUMBER") "EEE1VA100WR"))
      (libsource (lib "eagle-import") (part "EEE1VA100WR"))
    )
    (comp (ref "C10")
      (value "10uF")
      (footprint "eagle-import:CAP_EEE_B")
      (fields (field (name "MANUFACTURER_PART_NUMBER") "EEE1VA100WR"))
      (libsource (lib "eagle-import") (part "EEE1VA100WR"))
    )
    (comp (ref "C11")
      (value "10uF")
      (footprint "eagle-import:CAP_EEE_B")
      (fields (field (name "MANUFACTURER_PART_NUMBER") "EEE1VA100WR"))
      (libsource (lib "eagle-import") (part "EEE1VA100WR"))
    )
    (comp (ref "C16")
      (value "10uF")
      (footprint "eagle-import:CAP_EEE_B")
      (fields (field (name "MANUFACTURER_PART_NUMBER") "EEE1VA100WR"))
      (libsource (lib "eagle-import") (part "EEE1VA100WR"))
    )
    (comp (ref "D6")
      (value "BYV32")
      (footprint "eagle-import:TO220ABS")
      (libsource (lib "eagle-import") (part "BYV32"))
    )
    (comp (ref "D7")
      (value "BYV32")
      (footprint "eagle-import:TO220ABS")
      (libsource (lib "eagle-import") (part "BYV32"))
    )
    (comp (ref "GATE3")
      (value "MIC4604YM")
      (footprint "eagle-import:SOIC-8_M")
      (fields
        (field (name "DIGIKEY_PART_NUMBER") "576-4395-1-ND")
        (field (name "MANUFACTURER") "Microchip")
        (field (name "MANUFACTURER_PART_NUMBER") "MIC4604YM-T5")
      )
      (libsource (lib "eagle-import") (part "MIC4604YM"))
    )
    (comp (ref "GATE4")
      (value "MIC4604YM")
      (footprint "eagle-import:SOIC-8_M")
      (fields
        (field (name "DIGIKEY_PART_NUMBER") "576-4395-1-ND")
        (field (name "MANUFACTURER") "Microchip")
        (field (name "MANUFACTURER_PART_NUMBER") "MIC4604YM-T5")
      )
      (libsource (lib "eagle-import") (part "MIC4604YM"))
    )
    (comp (ref "MOTOR_NEG1")
      (value "SE14")
      (footprint "eagle-import:SE14")
      (libsource (lib "eagle-import") (part "SE14"))
    )
    (comp (ref "MOTOR_NEG_B1")
      (value "SE14")
      (footprint "eagle-import:SE14")
      (libsource (lib "eagle-import") (part "SE14"))
    )
    (comp (ref "MOTOR_POS1")
      (value "SE14")
      (footprint "eagle-import:SE14")
      (libsource (lib "eagle-import") (part "SE14"))
    )
    (comp (ref "R19")
      (value "10m")
      (footprint "eagle-import:R2512")
      (libsource (lib "eagle-import") (part "R-US_R2512"))
    )
    (comp (ref "TOP_FWD1")
      (value "CSD18502KCS_KCS_3")
      (footprint "eagle-import:KCS3")
      (fields
        (field (name "DIGIKEY_PART_NUMBER") "296-35013-ND")
        (field (name "MANUFACTURER") "Texas Instruments")
        (field (name "MANUFACTURER_PART_NUMBER") "CSD18533KCS")
      )
      (libsource (lib "eagle-import") (part "CSD18502KCS_KCS_3"))
    )
    (comp (ref "TOP_REV1")
      (value "CSD18502KCS_KCS_3")
      (footprint "eagle-import:KCS3")
      (fields
        (field (name "DIGIKEY_PART_NUMBER") "296-35013-ND")
        (field (name "MANUFACTURER") "Texas Instruments")
        (field (name "MANUFACTURER_PART_NUMBER") "CSD18533KCS")
      )
      (libsource (lib "eagle-import") (part "CSD18502KCS_KCS_3"))
    )
    (comp (ref "U$9")
      (value "HEATSINK")
      (footprint "eagle-import:HEATSINK")
      (fields
        (field (name "DIGIKEY_PART_NUMBER") "HS112-ND")
        (field (name "MANUFACTURER") "Aavid Thermalloy")
        (field (name "MANUFACTURER_PART_NUMBER") "507002B00000G")
      )
      (libsource (lib "eagle-import") (part "HEATSINK"))
    )
    (comp (ref "U$10")
      (value "HEATSINK")
      (footprint "eagle-import:HEATSINK")
      (fields
        (field (name "DIGIKEY_PART_NUMBER") "HS112-ND")
        (field (name "MANUFACTURER") "Aavid Thermalloy")
        (field (name "MANUFACTURER_PART_NUMBER") "507002B00000G")
      )
      (libsource (lib "eagle-import") (part "HEATSINK"))
    )
    (comp (ref "U$11")
      (value "HEATSINK")
      (footprint "eagle-import:HEATSINK")
      (fields
        (field (name "DIGIKEY_PART_NUMBER") "HS112-ND")
        (field (name "MANUFACTURER") "Aavid Thermalloy")
        (field (name "MANUFACTURER_PART_NUMBER") "507002B00000G")
      )
      (libsource (lib "eagle-import") (part "HEATSINK"))
    )
    (comp (ref "U$12")
      (value "HEATSINK")
      (footprint "eagle-import:HEATSINK")
      (fields
        (field (name "DIGIKEY_PART_NUMBER") "HS112-ND")
        (field (name "MANUFACTURER") "Aavid Thermalloy")
        (field (name "MANUFACTURER_PART_NUMBER") "507002B00000G")
      )
      (libsource (lib "eagle-import") (part "HEATSINK"))
    )
  )
  (nets
    (net (code "1") (name "3_3V") (class "Default")
      (node (ref "3_3V") (pin "1") (pinfunction "1_1") (pintype "passive"))
      (node (ref "3_3V") (pin "2") (pinfunction "2_2") (pintype "passive"))
      (node (ref "3_3V") (pin "3") (pinfunction "3_3") (pintype "passive"))
      (node (ref "BLUETOOTH") (pin "4") (pinfunction "4_4") (pintype "passive"))
      (node (ref "CAMERA") (pin "2") (pinfunction "2_2") (pintype "passive"))
      (node (ref "HALL1") (pin "1") (pinfunction "1_1") (pintype "passive"))
      (node (ref "HALL1_B") (pin "1") (pinfunction "1_1") (pintype "passive"))
      (node (ref "HALL2") (pin "1") (pinfunction "1_1") (pintype "passive"))
      (node (ref "HALL2_B") (pin "1") (pinfunction "1_1") (pintype "passive"))
      (node (ref "R12") (pin "1") (pinfunction "1_1") (pintype "passive"))
      (node (ref "R13") (pin "1") (pinfunction "1_1") (pintype "passive"))
      (node (ref "R14") (pin "1") (pinfunction "1_1") (pintype "passive"))
      (node (ref "R15") (pin "1") (pinfunction "1_1") (pintype "passive"))
      (node (ref "U$1") (pin "3V3_LO") (pinfunction "3V3_LO_3V3_LO") (pintype "bidirectional"))
    )
    (net (code "2") (name "5V") (class "Default")
      (node (ref "5V") (pin "1") (pinfunction "1_1") (pintype "passive"))
      (node (ref "5V") (pin "2") (pinfunction "2_2") (pintype "passive"))
      (node (ref "5V") (pin "3") (pinfunction "3_3") (pintype "passive"))
      (node (ref "C8") (pin "1") (pinfunction "1_1") (pintype "passive"))
      (node (ref "REC") (pin "2") (pinfunction "2_2") (pintype "passive"))
      (node (ref "S1") (pin "7") (pinfunction "7_7") (pintype "passive"))
      (node (ref "SERVO") (pin "2") (pinfunction "2_2") (pintype "passive"))
      (node (ref "VOLT_REG") (pin "2") (pinfunction "OUT_2") (pintype "passive"))
    )
    (net (code "3") (name "5V_TEENSY") (class "Default")
      (node (ref "S1") (pin "6") (pinfunction "6_6") (pintype "passive"))
      (node (ref "U$1") (pin "VIN") (pinfunction "VIN_VIN") (pintype "bidirectional"))
      (node (ref "U7") (pin "18") (pinfunction "AVCC_18") (pintype "bidirectional"))
      (node (ref "U7") (pin "29") (pinfunction "PC6(/RESET)_29") (pintype "bidirectional"))
      (node (ref "U7") (pin "4") (pinfunction "VCC_4") (pintype "bidirectional"))
      (node (ref "U7") (pin "6") (pinfunction "VCC_6") (pintype "bidirectional"))
    )
    (net (code "4") (name "7_4V") (class "Default")
      (node (ref "R1") (pin "2") (pinfunction "2_2") (pintype "passive"))
      (node (ref "SV1") (pin "3") (pinfunction "3_3") (pintype "passive"))
      (node (ref "SV1") (pin "4") (pinfunction "4_4") (pintype "passive"))
      (node (ref "SV1") (pin "5") (pinfunction "5_5") (pintype "passive"))
      (node (ref "SV1") (pin "6") (pinfunction "6_6") (pintype "passive"))
      (node (ref "SV3") (pin "1") (pinfunction "1_1") (pintype "passive"))
      (node (ref "VOLT_REG") (pin "3") (pinfunction "IN_3") (pintype "input"))
    )
    (net (code "5") (name "7_4V_TOP") (class "Default")
      (node (ref "BIG_SWITCH") (pin "GND") (pinfunction "GND_GND") (pintype "power_in"))
      (node (ref "C7") (pin "1") (pinfunction "1_1") (pintype "passive"))
      (node (ref "D3") (pin "A1") (pinfunction "A1_A1") (pintype "passive"))
      (node (ref "D3") (pin "A2") (pinfunction "A2_A2") (pintype "passive"))
      (node (ref "D4") (pin "A1") (pinfunction "A1_A1") (pintype "passive"))
      (node (ref "D4") (pin "A2") (pinfunction "A2_A2") (pintype "passive"))
      (node (ref "D6") (pin "A1") (pinfunction "A1_A1") (pintype "passive"))
      (node (ref "D6") (pin "A2") (pinfunction "A2_A2") (pintype "passive"))
      (node (ref "D7") (pin "A1") (pinfunction "A1_A1") (pintype "passive"))
      (node (ref "D7") (pin "A2") (pinfunction "A2_A2") (pintype "passive"))
      (node (ref "GATE1") (pin "1") (pinfunction "VDD_1") (pintype "power_in"))
      (node (ref "GATE2") (pin "1") (pinfunction "VDD_1") (pintype "power_in"))
      (node (ref "GATE3") (pin "1") (pinfunction "VDD_1") (pintype "power_in"))
      (node (ref "GATE4") (pin "1") (pinfunction "VDD_1") (pintype "power_in"))
      (node (ref "I_SENSE_AMP") (pin "5") (pinfunction "V+_5") (pintype "power_in"))
      (node (ref "SV5") (pin "1") (pinfunction "1_1") (pintype "passive"))
      (node (ref "SV5") (pin "2") (pinfunction "2_2") (pintype "passive"))
      (node (ref "SV5") (pin "3") (pinfunction "3_3") (pintype "passive"))
      (node (ref "SV5") (pin "4") (pinfunction "4_4") (pintype "passive"))
      (node (ref "TOP_FWD") (pin "2") (pinfunction "DRAIN_2") (pintype "passive"))
      (node (ref "TOP_FWD1") (pin "2") (pinfunction "DRAIN_2") (pintype "passive"))
      (node (ref "TOP_REV") (pin "2") (pinfunction "DRAIN_2") (pintype "passive"))
      (node (ref "TOP_REV1") (pin "2") (pinfunction "DRAIN_2") (pintype "passive"))
    )
    (net (code "6") (name "7_4V_TOP2") (class "Default")
      (node (ref "LED1_CONN") (pin "2") (pinfunction "2_2") (pintype "passive"))
      (node (ref "LED2_CONN") (pin "2") (pinfunction "2_2") (pintype "passive"))
      (node (ref "R6") (pin "P$2") (pinfunction "2_P$2") (pintype "passive"))
      (node (ref "R8") (pin "P$2") (pinfunction "2_P$2") (pintype "passive"))
      (node (ref "SV7") (pin "1") (pinfunction "1_1") (pintype "passive"))
      (node (ref "SV9") (pin "2") (pinfunction "2_2") (pintype "passive"))
    )
    (net (code "7") (name "ADC6") (class "Default")
      (node (ref "ATGPIO") (pin "6") (pinfunction "6_6") (pintype "passive"))
      (node (ref "U7") (pin "19") (pinfunction "ADC6_19") (pintype "bidirectional"))
    )
    (net (code "8") (name "ADC7") (class "Default")
      (node (ref "ATGPIO") (pin "7") (pinfunction "7_7") (pintype "passive"))
      (node (ref "U7") (pin "22") (pinfunction "ADC7_22") (pintype "bidirectional"))
    )
    (net (code "9") (name "BATT_VOLTAGE") (class "Default")
      (node (ref "BATT_HIGH") (pin "MP") (pinfunction "MP_MP") (pintype "passive"))
      (node (ref "FUSE") (pin "A") (pinfunction "VCC_A") (pintype "power_in"))
      (node (ref "FUSE") (pin "C") (pinfunction "VCC_C") (pintype "power_in"))
    )
    (net (code "10") (name "BATT_VOLTAGE_SENSE") (class "Default")
      (node (ref "R1") (pin "1") (pinfunction "1_1") (pintype "passive"))
      (node (ref "R2") (pin "2") (pinfunction "2_2") (pintype "passive"))
      (node (ref "U$1") (pin "17/A3") (pinfunction "17/A3_17/A3") (pintype "bidirectional"))
    )
    (net (code "11") (name "BLT_RX") (class "Default")
      (node (ref "BLUETOOTH") (pin "1") (pinfunction "1_1") (pintype "passive"))
      (node (ref "U$1") (pin "8") (pinfunction "8_8") (pintype "bidirectional"))
    )
    (net (code "12") (name "BLT_TX") (class "Default")
      (node (ref "BLUETOOTH") (pin "2") (pinfunction "2_2") (pintype "passive"))
      (node (ref "U$1") (pin "7") (pinfunction "7_7") (pintype "bidirectional"))
    )
    (net (code "13") (name "CAMERA_A0") (class "Default")
      (node (ref "CAMERA") (pin "3") (pinfunction "3_3") (pintype "passive"))
      (node (ref "U7") (pin "23") (pinfunction "PC0(ADC0)_23") (pintype "bidirectional"))
    )
    (net (code "14") (name "CAMERA_A0_B") (class "Default")
      (node (ref "CAMERA_B") (pin "1") (pinfunction "1_1") (pintype "passive"))
      (node (ref "U$1") (pin "31/A12") (pinfunction "31/A12_31/A12") (pintype "bidirectional"))
    )
    (net (code "15") (name "CAMERA_CL") (class "Default")
      (node (ref "CAMERA") (pin "4") (pinfunction "4_4") (pintype "passive"))
      (node (ref "U7") (pin "12") (pinfunction "PB0(ICP)_12") (pintype "bidirectional"))
    )
    (net (code "16") (name "CAMERA_CL_B") (class "Default")
      (node (ref "CAMERA_B") (pin "2") (pinfunction "2_2") (pintype "passive"))
      (node (ref "U$1") (pin "30") (pinfunction "30_30") (pintype "bidirectional"))
    )
    (net (code "17") (name "CAMERA_SI") (class "Default")
      (node (ref "CAMERA") (pin "5") (pinfunction "5_5") (pintype "passive"))
      (node (ref "U7") (pin "11") (pinfunction "PD7(AIN1)_11") (pintype "bidirectional"))
    )
    (net (code "18") (name "CAMERA_SI_B") (class "Default")
      (node (ref "CAMERA_B") (pin "3") (pinfunction "3_3") (pintype "passive"))
      (node (ref "U$1") (pin "29") (pinfunction "29_29") (pintype "bidirectional"))
    )
    (net (code "19") (name "EMF_SENSE_HIGH") (class "Default")
      (node (ref "R3") (pin "1") (pinfunction "1_1") (pintype "passive"))
      (node (ref "R4") (pin "2") (pinfunction "2_2") (pintype "passive"))
      (node (ref "U$1") (pin "19/A5/SCL") (pinfunction "19/A5/SCL_19/A5/SCL") (pintype "bidirectional"))
    )
    (net (code "20") (name "EMF_SENSE_LOW") (class "Default")
      (node (ref "S1") (pin "5") (pinfunction "5_5") (pintype "passive"))
      (node (ref "U$1") (pin "18/A4/SDA") (pinfunction "18/A4/SDA_18/A4/SDA") (pintype "bidirectional"))
    )
    (net (code "21") (name "GND") (class "Default")
      (node (ref "BLUETOOTH") (pin "3") (pinfunction "3_3") (pintype "passive"))
      (node (ref "C5") (pin "2") (pinfunction "2_2") (pintype "passive"))
      (node (ref "C6") (pin "2") (pinfunction "2_2") (pintype "passive"))
      (node (ref "C8") (pin "2") (pinfunction "2_2") (pintype "passive"))
      (node (ref "CAMERA") (pin "1") (pinfunction "1_1") (pintype "passive"))
      (node (ref "D1") (pin "C") (pinfunction "C_C") (pintype "passive"))
      (node (ref "D2") (pin "C") (pinfunction "C_C") (pintype "passive"))
      (node (ref "D5") (pin "C") (pinfunction "C_C") (pintype "passive"))
      (node (ref "GROUND") (pin "1") (pinfunction "1_1") (pintype "passive"))
      (node (ref "GROUND") (pin "2") (pinfunction "2_2") (pintype "passive"))
      (node (ref "GROUND") (pin "3") (pinfunction "3_3") (pintype "passive"))
      (node (ref "GROUND") (pin "4") (pinfunction "4_4") (pintype "passive"))
      (node (ref "HALL1") (pin "2") (pinfunction "2_2") (pintype "passive"))
      (node (ref "HALL1_B") (pin "2") (pinfunction "2_2") (pintype "passive"))
      (node (ref "HALL2") (pin "2") (pinfunction "2_2") (pintype "passive"))
      (node (ref "HALL2_B") (pin "2") (pinfunction "2_2") (pintype "passive"))
      (node (ref "R2") (pin "1") (pinfunction "1_1") (pintype "passive"))
      (node (ref "REC") (pin "1") (pinfunction "1_1") (pintype "passive"))
      (node (ref "S1") (pin "10") (pinfunction "10_10") (pintype "passive"))
      (node (ref "S1") (pin "11") (pinfunction "11_11") (pintype "passive"))
      (node (ref "S1") (pin "12") (pinfunction "12_12") (pintype "passive"))
      (node (ref "S1") (pin "9") (pinfunction "9_9") (pintype "passive"))
      (node (ref "SERVO") (pin "1") (pinfunction "1_1") (pintype "passive"))
      (node (ref "SV1") (pin "10") (pinfunction "10_10") (pintype "passive"))
      (node (ref "SV1") (pin "7") (pinfunction "7_7") (pintype "passive"))
      (node (ref "SV1") (pin "8") (pinfunction "8_8") (pintype "passive"))
      (node (ref "SV1") (pin "9") (pinfunction "9_9") (pintype "passive"))
      (node (ref "SV3") (pin "4") (pinfunction "4_4") (pintype "passive"))
      (node (ref "U$1") (pin "AGND") (pinfunction "AGND_AGND") (pintype "bidirectional"))
      (node (ref "U$1") (pin "GND") (pinfunction "GND_GND") (pintype "bidirectional"))
      (node (ref "U$1") (pin "GND2") (pinfunction "GND2_GND2") (pintype "bidirectional"))
      (node (ref "U7") (pin "21") (pinfunction "AGND_21") (pintype "bidirectional"))
      (node (ref "U7") (pin "3") (pinfunction "GND_3") (pintype "bidirectional"))
      (node (ref "U7") (pin "5") (pinfunction "GND_5") (pintype "bidirectional"))
      (node (ref "VOLT_REG") (pin "1") (pinfunction "GND_1") (pintype "input"))
    )
    (net (code "22") (name "GND_TOP") (class "Default")
      (node (ref "BATT_LOW") (pin "MP") (pinfunction "MP_MP") (pintype "passive"))
      (node (ref "BOT_FWD") (pin "3") (pinfunction "SOURCE_3") (pintype "passive"))
      (node (ref "BOT_FWD1") (pin "3") (pinfunction "SOURCE_3") (pintype "passive"))
      (node (ref "BOT_REV") (pin "3") (pinfunction "SOURCE_3") (pintype "passive"))
      (node (ref "BOT_REV1") (pin "3") (pinfunction "SOURCE_3") (pintype "passive"))
      (node (ref "C12") (pin "-") (pinfunction "-_-") (pintype "passive"))
      (node (ref "C13") (pin "-") (pinfunction "-_-") (pintype "passive"))
      (node (ref "C14") (pin "-") (pinfunction "-_-") (pintype "passive"))
      (node (ref "C15") (pin "-") (pinfunction "-_-") (pintype "passive"))
      (node (ref "C7") (pin "2") (pinfunction "2_2") (pintype "passive"))
      (node (ref "GATE1") (pin "7") (pinfunction "VSS_7") (pintype "power_in"))
      (node (ref "GATE2") (pin "7") (pinfunction "VSS_7") (pintype "power_in"))
      (node (ref "GATE3") (pin "7") (pinfunction "VSS_7") (pintype "power_in"))
      (node (ref "GATE4") (pin "7") (pinfunction "VSS_7") (pintype "power_in"))
      (node (ref "I_SENSE_AMP") (pin "2") (pinfunction "V-_2") (pintype "power_in"))
      (node (ref "MOTOR_NEG_B") (pin "MP") (pinfunction "MP_MP") (pintype "passive"))
      (node (ref "MOTOR_NEG_B1") (pin "MP") (pinfunction "MP_MP") (pintype "passive"))
      (node (ref "R16") (pin "1") (pinfunction "1_1") (pintype "passive"))
      (node (ref "R18") (pin "1") (pinfunction "1_1") (pintype "passive"))
      (node (ref "SV5") (pin "5") (pinfunction "5_5") (pintype "passive"))
      (node (ref "SV5") (pin "6") (pinfunction "6_6") (pintype "passive"))
      (node (ref "SV5") (pin "7") (pinfunction "7_7") (pintype "passive"))
      (node (ref "SV5") (pin "8") (pinfunction "8_8") (pintype "passive"))
    )
    (net (code "23") (name "GND_TOP2") (class "Default")
      (node (ref "SV7") (pin "4") (pinfunction "4_4") (pintype "passive"))
      (node (ref "SV9") (pin "1") (pinfunction "1_1") (pintype "passive"))
      (node (ref "T1") (pin "1") (pinfunction "E_1") (pintype "passive"))
      (node (ref "T2") (pin "1") (pinfunction "E_1") (pintype "passive"))
      (node (ref "U$3") (pin "P2") (pinfunction "P2_P2") (pintype "bidirectional"))
      (node (ref "U$7") (pin "P2") (pinfunction "P2_P2") (pintype "bidirectional"))
    )
    (net (code "24") (name "HALL1") (class "Default")
      (node (ref "HALL1") (pin "3") (pinfunction "3_3") (pintype "passive"))
      (node (ref "R12") (pin "2") (pinfunction "2_2") (pintype "passive"))
      (node (ref "U7") (pin "32") (pinfunction "PD2(INT0)_32") (pintype "bidirectional"))
    )
    (net (code "25") (name "HALL1_B") (class "Default")
      (node (ref "HALL1_B") (pin "3") (pinfunction "3_3") (pintype "passive"))
      (node (ref "R14") (pin "2") (pinfunction "2_2") (pintype "passive"))
      (node (ref "U$1") (pin "1/TX") (pinfunction "1/TX_1/TX") (pintype "bidirectional"))
    )
    (net (code "26") (name "HALL2") (class "Default")
      (node (ref "HALL2") (pin "3") (pinfunction "3_3") (pintype "passive"))
      (node (ref "R13") (pin "2") (pinfunction "2_2") (pintype "passive"))
      (node (ref "U7") (pin "1") (pinfunction "PD3(INT1)_1") (pintype "bidirectional"))
    )
    (net (code "27") (name "HALL2_B") (class "Default")
      (node (ref "HALL2_B") (pin "3") (pinfunction "3_3") (pintype "passive"))
      (node (ref "R15") (pin "2") (pinfunction "2_2") (pintype "passive"))
      (node (ref "U$1") (pin "2") (pinfunction "2_2") (pintype "bidirectional"))
    )
    (net (code "28") (name "HI") (class "Default")
      (node (ref "SV2") (pin "2") (pinfunction "2_2") (pintype "passive"))
      (node (ref "U$1") (pin "3/CANTX") (pinfunction "3/CANTX_3/CANTX") (pintype "bidirectional"))
    )
    (net (code "29") (name "HI_TOP") (class "Default")
      (node (ref "GATE1") (pin "5") (pinfunction "HI_5") (pintype "input"))
      (node (ref "GATE2") (pin "6") (pinfunction "LI_6") (pintype "input"))
      (node (ref "GATE3") (pin "5") (pinfunction "HI_5") (pintype "input"))
      (node (ref "GATE4") (pin "6") (pinfunction "LI_6") (pintype "input"))
      (node (ref "SV6") (pin "2") (pinfunction "2_2") (pintype "passive"))
    )
    (net (code "30") (name "I_SENSE") (class "Default")
      (node (ref "SV2") (pin "3") (pinfunction "3_3") (pintype "passive"))
      (node (ref "U$1") (pin "5") (pinfunction "5_5") (pintype "bidirectional"))
    )
    (net (code "31") (name "I_SENSE_HI_TOP") (class "Default")
      (node (ref "BOT_REV") (pin "2") (pinfunction "DRAIN_2") (pintype "passive"))
      (node (ref "BOT_REV1") (pin "2") (pinfunction "DRAIN_2") (pintype "passive"))
      (node (ref "I_SENSE_AMP") (pin "3") (pinfunction "IN+_3") (pintype "input"))
      (node (ref "R17") (pin "1") (pinfunction "1_1") (pintype "passive"))
      (node (ref "R19") (pin "1") (pinfunction "1_1") (pintype "passive"))
      (node (ref "TOP_FWD") (pin "3") (pinfunction "SOURCE_3") (pintype "passive"))
      (node (ref "TOP_FWD1") (pin "3") (pinfunction "SOURCE_3") (pintype "passive"))
    )
    (net (code "32") (name "I_SENSE_LOW_TOP") (class "Default")
      (node (ref "I_SENSE_AMP") (pin "4") (pinfunction "IN-_4") (pintype "input"))
      (node (ref "MOTOR_POS") (pin "MP") (pinfunction "MP_MP") (pintype "passive"))
      (node (ref "MOTOR_POS1") (pin "MP") (pinfunction "MP_MP") (pintype "passive"))
      (node (ref "R17") (pin "2") (pinfunction "2_2") (pintype "passive"))
      (node (ref "R19") (pin "2") (pinfunction "2_2") (pintype "passive"))
      (node (ref "SV6") (pin "4") (pinfunction "4_4") (pintype "passive"))
    )
    (net (code "33") (name "I_SENSE_TOP") (class "Default")
      (node (ref "I_SENSE_AMP") (pin "1") (pinfunction "OUT_1") (pintype "output"))
      (node (ref "R18") (pin "2") (pinfunction "2_2") (pintype "passive"))
      (node (ref "SV6") (pin "3") (pinfunction "3_3") (pintype "passive"))
    )
    (net (code "34") (name "LED1") (class "Default")
      (node (ref "R9") (pin "2") (pinfunction "2_2") (pintype "passive"))
      (node (ref "U$1") (pin "14/A0") (pinfunction "14/A0_14/A0") (pintype "bidirectional"))
    )
    (net (code "35") (name "LED1HI") (class "Default")
      (node (ref "LED1") (pin "POSITIVE") (pinfunction "POSITIVE_POSITIVE") (pintype "bidirectional"))
      (node (ref "LED1") (pin "POSITIVE1") (pinfunction "POSITIVE_POSITIVE1") (pintype "bidirectional"))
      (node (ref "LED1_CONN2") (pin "2") (pinfunction "2_2") (pintype "passive"))
    )
    (net (code "36") (name "LED1LO") (class "Default")
      (node (ref "LED1") (pin "NEGATIVE") (pinfunction "NEGATIVE_NEGATIVE") (pintype "bidirectional"))
      (node (ref "LED1") (pin "NEGATIVE1") (pinfunction "NEGATIVE_NEGATIVE1") (pintype "bidirectional"))
      (node (ref "LED1_CONN2") (pin "1") (pinfunction "1_1") (pintype "passive"))
    )
    (net (code "37") (name "LED2") (class "Default")
      (node (ref "R10") (pin "2") (pinfunction "2_2") (pintype "passive"))
      (node (ref "U$1") (pin "15/A1") (pinfunction "15/A1_15/A1") (pintype "bidirectional"))
    )
    (net (code "38") (name "LED2HI") (class "Default")
      (node (ref "LED2") (pin "POSITIVE") (pinfunction "POSITIVE_POSITIVE") (pintype "bidirectional"))
      (node (ref "LED2") (pin "POSITIVE1") (pinfunction "POSITIVE_POSITIVE1") (pintype "bidirectional"))
      (node (ref "LED2_CONN2") (pin "2") (pinfunction "2_2") (pintype "passive"))
    )
    (net (code "39") (name "LED2LO") (class "Default")
      (node (ref "LED2") (pin "NEGATIVE") (pinfunction "NEGATIVE_NEGATIVE") (pintype "bidirectional"))
      (node (ref "LED2") (pin "NEGATIVE1") (pinfunction "NEGATIVE_NEGATIVE1") (pintype "bidirectional"))
      (node (ref "LED2_CONN2") (pin "1") (pinfunction "1_1") (pintype "passive"))
    )
    (net (code "40") (name "LED3") (class "Default")
      (node (ref "R11") (pin "2") (pinfunction "2_2") (pintype "passive"))
      (node (ref "U$1") (pin "16/A2") (pinfunction "16/A2_16/A2") (pintype "bidirectional"))
    )
    (net (code "41") (name "LI") (class "Default")
      (node (ref "SV2") (pin "1") (pinfunction "1_1") (pintype "passive"))
      (node (ref "U$1") (pin "4/CANRX") (pinfunction "4/CANRX_4/CANRX") (pintype "bidirectional"))
    )
    (net (code "42") (name "LI_TOP") (class "Default")
      (node (ref "GATE1") (pin "6") (pinfunction "LI_6") (pintype "input"))
      (node (ref "GATE2") (pin "5") (pinfunction "HI_5") (pintype "input"))
      (node (ref "GATE3") (pin "6") (pinfunction "LI_6") (pintype "input"))
      (node (ref "GATE4") (pin "5") (pinfunction "HI_5") (pintype "input"))
      (node (ref "SV6") (pin "1") (pinfunction "1_1") (pintype "passive"))
    )
    (net (code "43") (name "MOTOR_HIGH") (class "Default")
      (node (ref "R3") (pin "2") (pinfunction "2_2") (pintype "passive"))
      (node (ref "SV2") (pin "4") (pinfunction "4_4") (pintype "passive"))
    )
    (net (code "44") (name "MOTOR_LOW") (class "Default")
      (node (ref "R4") (pin "1") (pinfunction "1_1") (pintype "passive"))
      (node (ref "S1") (pin "8") (pinfunction "8_8") (pintype "passive"))
      (node (ref "SV2") (pin "5") (pinfunction "5_5") (pintype "passive"))
    )
    (net (code "45") (name "MOTOR_LOW_TOP") (class "Default")
      (node (ref "BOT_FWD") (pin "2") (pinfunction "DRAIN_2") (pintype "passive"))
      (node (ref "BOT_FWD1") (pin "2") (pinfunction "DRAIN_2") (pintype "passive"))
      (node (ref "MOTOR_NEG") (pin "MP") (pinfunction "MP_MP") (pintype "passive"))
      (node (ref "MOTOR_NEG1") (pin "MP") (pinfunction "MP_MP") (pintype "passive"))
      (node (ref "SV6") (pin "5") (pinfunction "5_5") (pintype "passive"))
      (node (ref "TOP_REV") (pin "3") (pinfunction "SOURCE_3") (pintype "passive"))
      (node (ref "TOP_REV1") (pin "3") (pinfunction "SOURCE_3") (pintype "passive"))
    )
    (net (code "46") (name "Net-(BIG_SWITCH-PadVCC)") (class "Default")
      (node (ref "BIG_SWITCH") (pin "VCC") (pinfunction "VCC_VCC") (pintype "power_in"))
      (node (ref "C12") (pin "+") (pinfunction "+_+") (pintype "passive"))
      (node (ref "C13") (pin "+") (pinfunction "+_+") (pintype "passive"))
      (node (ref "C14") (pin "+") (pinfunction "+_+") (pintype "passive"))
      (node (ref "C15") (pin "+") (pinfunction "+_+") (pintype "passive"))
      (node (ref "FUSE") (pin "B") (pinfunction "GND_B") (pintype "power_in"))
      (node (ref "FUSE") (pin "D") (pinfunction "GND_D") (pintype "power_in"))
      (node (ref "R16") (pin "2") (pinfunction "2_2") (pintype "passive"))
    )
    (net (code "47") (name "Net-(BOT_FWD-GATE)") (class "Default")
      (node (ref "BOT_FWD") (pin "1") (pinfunction "GATE_1") (pintype "passive"))
      (node (ref "GATE2") (pin "8") (pinfunction "LO_8") (pintype "output"))
    )
    (net (code "48") (name "Net-(BOT_FWD1-GATE)") (class "Default")
      (node (ref "BOT_FWD1") (pin "1") (pinfunction "GATE_1") (pintype "passive"))
      (node (ref "GATE4") (pin "8") (pinfunction "LO_8") (pintype "output"))
    )
    (net (code "49") (name "Net-(BOT_REV-GATE)") (class "Default")
      (node (ref "BOT_REV") (pin "1") (pinfunction "GATE_1") (pintype "passive"))
      (node (ref "GATE1") (pin "8") (pinfunction "LO_8") (pintype "output"))
    )
    (net (code "50") (name "Net-(BOT_REV1-GATE)") (class "Default")
      (node (ref "BOT_REV1") (pin "1") (pinfunction "GATE_1") (pintype "passive"))
      (node (ref "GATE3") (pin "8") (pinfunction "LO_8") (pintype "output"))
    )
    (net (code "51") (name "Net-(D1-PadA)") (class "Default")
      (node (ref "D1") (pin "A") (pinfunction "A_A") (pintype "passive"))
      (node (ref "R9") (pin "1") (pinfunction "1_1") (pintype "passive"))
    )
    (net (code "52") (name "Net-(D2-PadA)") (class "Default")
      (node (ref "D2") (pin "A") (pinfunction "A_A") (pintype "passive"))
      (node (ref "R10") (pin "1") (pinfunction "1_1") (pintype "passive"))
    )
    (net (code "53") (name "Net-(D5-PadA)") (class "Default")
      (node (ref "D5") (pin "A") (pinfunction "A_A") (pintype "passive"))
      (node (ref "R11") (pin "1") (pinfunction "1_1") (pintype "passive"))
    )
    (net (code "54") (name "Net-(GATE1-HB)") (class "Default")
      (node (ref "C1") (pin "2") (pinfunction "2_2") (pintype "passive"))
      (node (ref "C2") (pin "2") (pinfunction "2_2") (pintype "passive"))
      (node (ref "D3") (pin "C") (pinfunction "C_C") (pintype "passive"))
      (node (ref "GATE1") (pin "2") (pinfunction "HB_2") (pintype "passive"))
    )
    (net (code "55") (name "Net-(GATE1-HO)") (class "Default")
      (node (ref "GATE1") (pin "3") (pinfunction "HO_3") (pintype "output"))
      (node (ref "TOP_FWD") (pin "1") (pinfunction "GATE_1") (pintype "passive"))
    )
    (net (code "56") (name "Net-(GATE1-HS)") (class "Default")
      (node (ref "C1") (pin "1") (pinfunction "1_1") (pintype "passive"))
      (node (ref "C2") (pin "1") (pinfunction "1_1") (pintype "passive"))
      (node (ref "GATE1") (pin "4") (pinfunction "HS_4") (pintype "passive"))
    )
    (net (code "57") (name "Net-(GATE2-HB)") (class "Default")
      (node (ref "C3") (pin "2") (pinfunction "2_2") (pintype "passive"))
      (node (ref "C4") (pin "2") (pinfunction "2_2") (pintype "passive"))
      (node (ref "D4") (pin "C") (pinfunction "C_C") (pintype "passive"))
      (node (ref "GATE2") (pin "2") (pinfunction "HB_2") (pintype "passive"))
    )
    (net (code "58") (name "Net-(GATE2-HO)") (class "Default")
      (node (ref "GATE2") (pin "3") (pinfunction "HO_3") (pintype "output"))
      (node (ref "TOP_REV") (pin "1") (pinfunction "GATE_1") (pintype "passive"))
    )
    (net (code "59") (name "Net-(GATE2-HS)") (class "Default")
      (node (ref "C3") (pin "1") (pinfunction "1_1") (pintype "passive"))
      (node (ref "C4") (pin "1") (pinfunction "1_1") (pintype "passive"))
      (node (ref "GATE2") (pin "4") (pinfunction "HS_4") (pintype "passive"))
    )
    (net (code "60") (name "Net-(GATE3-HB)") (class "Default")
      (node (ref "C10") (pin "2") (pinfunction "2_2") (pintype "passive"))
      (node (ref "C9") (pin "2") (pinfunction "2_2") (pintype "passive"))
      (node (ref "D6") (pin "C") (pinfunction "C_C") (pintype "passive"))
      (node (ref "GATE3") (pin "2") (pinfunction "HB_2") (pintype "passive"))
    )
    (net (code "61") (name "Net-(GATE3-HO)") (class "Default")
      (node (ref "GATE3") (pin "3") (pinfunction "HO_3") (pintype "output"))
      (node (ref "TOP_FWD1") (pin "1") (pinfunction "GATE_1") (pintype "passive"))
    )
    (net (code "62") (name "Net-(GATE3-HS)") (class "Default")
      (node (ref "C10") (pin "1") (pinfunction "1_1") (pintype "passive"))
      (node (ref "C9") (pin "1") (pinfunction "1_1") (pintype "passive"))
      (node (ref "GATE3") (pin "4") (pinfunction "HS_4") (pintype "passive"))
    )
    (net (code "63") (name "Net-(GATE4-HB)") (class "Default")
      (node (ref "C11") (pin "2") (pinfunction "2_2") (pintype "passive"))
      (node (ref "C16") (pin "2") (pinfunction "2_2") (pintype "passive"))
      (node (ref "D7") (pin "C") (pinfunction "C_C") (pintype "passive"))
      (node (ref "GATE4") (pin "2") (pinfunction "HB_2") (pintype "passive"))
    )
    (net (code "64") (name "Net-(GATE4-HO)") (class "Default")
      (node (ref "GATE4") (pin "3") (pinfunction "HO_3") (pintype "output"))
      (node (ref "TOP_REV1") (pin "1") (pinfunction "GATE_1") (pintype "passive"))
    )
    (net (code "65") (name "Net-(GATE4-HS)") (class "Default")
      (node (ref "C11") (pin "1") (pinfunction "1_1") (pintype "passive"))
      (node (ref "C16") (pin "1") (pinfunction "1_1") (pintype "passive"))
      (node (ref "GATE4") (pin "4") (pinfunction "HS_4") (pintype "passive"))
    )
    (net (code "66") (name "Net-(LED_DRIVER1-DRAIN)") (class "Default")
      (node (ref "LED2_CONN") (pin "1") (pinfunction "1_1") (pintype "passive"))
      (node (ref "LED_DRIVER1") (pin "2") (pinfunction "DRAIN_2") (pintype "passive"))
    )
    (net (code "67") (name "Net-(LED_DRIVER1-GATE)") (class "Default")
      (node (ref "LED_DRIVER1") (pin "1") (pinfunction "GATE_1") (pintype "passive"))
      (node (ref "R8") (pin "P$1") (pinfunction "1_P$1") (pintype "passive"))
      (node (ref "T2") (pin "3") (pinfunction "C_3") (pintype "passive"))
    )
    (net (code "68") (name "Net-(LED_DRIVER1-SOURCE)") (class "Default")
      (node (ref "LED_DRIVER1") (pin "3") (pinfunction "SOURCE_3") (pintype "passive"))
      (node (ref "R7") (pin "2") (pinfunction "2_2") (pintype "passive"))
      (node (ref "T2") (pin "2") (pinfunction "B_2") (pintype "passive"))
    )
    (net (code "69") (name "Net-(LED_DRIVER2-DRAIN)") (class "Default")
      (node (ref "LED1_CONN") (pin "1") (pinfunction "1_1") (pintype "passive"))
      (node (ref "LED_DRIVER2") (pin "2") (pinfunction "DRAIN_2") (pintype "passive"))
    )
    (net (code "70") (name "Net-(LED_DRIVER2-GATE)") (class "Default")
      (node (ref "LED_DRIVER2") (pin "1") (pinfunction "GATE_1") (pintype "passive"))
      (node (ref "R6") (pin "P$1") (pinfunction "1_P$1") (pintype "passive"))
      (node (ref "T1") (pin "3") (pinfunction "C_3") (pintype "passive"))
    )
    (net (code "71") (name "Net-(LED_DRIVER2-SOURCE)") (class "Default")
      (node (ref "LED_DRIVER2") (pin "3") (pinfunction "SOURCE_3") (pintype "passive"))
      (node (ref "R5") (pin "2") (pinfunction "2_2") (pintype "passive"))
      (node (ref "T1") (pin "2") (pinfunction "B_2") (pintype "passive"))
    )
    (net (code "72") (name "Net-(R5-Pad1)") (class "Default")
      (node (ref "R5") (pin "1") (pinfunction "1_1") (pintype "passive"))
      (node (ref "U$7") (pin "P3") (pinfunction "P3_P3") (pintype "bidirectional"))
    )
    (net (code "73") (name "Net-(R7-Pad1)") (class "Default")
      (node (ref "R7") (pin "1") (pinfunction "1_1") (pintype "passive"))
      (node (ref "U$3") (pin "P3") (pinfunction "P3_P3") (pintype "bidirectional"))
    )
    (net (code "74") (name "Net-(U7-PB6(XTAL1{slash}TOSC1))") (class "Default")
      (node (ref "C6") (pin "1") (pinfunction "1_1") (pintype "passive"))
      (node (ref "U7") (pin "7") (pinfunction "PB6(XTAL1/TOSC1)_7") (pintype "bidirectional"))
      (node (ref "Y1") (pin "1") (pinfunction "1_1") (pintype "passive"))
    )
    (net (code "75") (name "Net-(U7-PB7(XTAL2{slash}TOSC2))") (class "Default")
      (node (ref "C5") (pin "1") (pinfunction "1_1") (pintype "passive"))
      (node (ref "U7") (pin "8") (pinfunction "PB7(XTAL2/TOSC2)_8") (pintype "bidirectional"))
      (node (ref "Y1") (pin "2") (pinfunction "2_2") (pintype "passive"))
    )
    (net (code "76") (name "PB1") (class "Default")
      (node (ref "ATGPIO") (pin "10") (pinfunction "10_10") (pintype "passive"))
      (node (ref "U7") (pin "13") (pinfunction "PB1(OC1A)_13") (pintype "bidirectional"))
    )
    (net (code "77") (name "PC1") (class "Default")
      (node (ref "ATGPIO") (pin "1") (pinfunction "1_1") (pintype "passive"))
      (node (ref "U7") (pin "24") (pinfunction "PC1(ADC1)_24") (pintype "bidirectional"))
    )
    (net (code "78") (name "PC2") (class "Default")
      (node (ref "ATGPIO") (pin "2") (pinfunction "2_2") (pintype "passive"))
      (node (ref "U7") (pin "25") (pinfunction "PC2(ADC2)_25") (pintype "bidirectional"))
    )
    (net (code "79") (name "PC3") (class "Default")
      (node (ref "ATGPIO") (pin "3") (pinfunction "3_3") (pintype "passive"))
      (node (ref "U7") (pin "26") (pinfunction "PC3(ADC3)_26") (pintype "bidirectional"))
    )
    (net (code "80") (name "PC4") (class "Default")
      (node (ref "ATGPIO") (pin "4") (pinfunction "4_4") (pintype "passive"))
      (node (ref "U7") (pin "27") (pinfunction "PC4(ADC4/SDA)_27") (pintype "bidirectional"))
    )
    (net (code "81") (name "PC5") (class "Default")
      (node (ref "ATGPIO") (pin "5") (pinfunction "5_5") (pintype "passive"))
      (node (ref "U7") (pin "28") (pinfunction "PC5(ADC5/SCL)_28") (pintype "bidirectional"))
    )
    (net (code "82") (name "PD4") (class "Default")
      (node (ref "ATGPIO") (pin "8") (pinfunction "8_8") (pintype "passive"))
      (node (ref "U7") (pin "2") (pinfunction "PD4(XCK/T0)_2") (pintype "bidirectional"))
    )
    (net (code "83") (name "PD5") (class "Default")
      (node (ref "ATGPIO") (pin "9") (pinfunction "9_9") (pintype "passive"))
      (node (ref "U7") (pin "9") (pinfunction "PD5(T1)_9") (pintype "bidirectional"))
    )
    (net (code "84") (name "PD6") (class "Default")
      (node (ref "U7") (pin "10") (pinfunction "PD6(AIN0)_10") (pintype "bidirectional"))
    )
    (net (code "85") (name "REC_EXTRA1") (class "Default")
      (node (ref "REC") (pin "5") (pinfunction "5_5") (pintype "passive"))
      (node (ref "U$1") (pin "22/A8") (pinfunction "22/A8_22/A8") (pintype "bidirectional"))
    )
    (net (code "86") (name "REC_EXTRA2") (class "Default")
      (node (ref "REC") (pin "6") (pinfunction "6_6") (pintype "passive"))
      (node (ref "U$1") (pin "23/A9") (pinfunction "23/A9_23/A9") (pintype "bidirectional"))
    )
    (net (code "87") (name "REC_MOTOR") (class "Default")
      (node (ref "REC") (pin "4") (pinfunction "4_4") (pintype "passive"))
      (node (ref "U$1") (pin "21/A7") (pinfunction "21/A7_21/A7") (pintype "bidirectional"))
    )
    (net (code "88") (name "REC_SERVO") (class "Default")
      (node (ref "REC") (pin "3") (pinfunction "3_3") (pintype "passive"))
      (node (ref "U$1") (pin "20/A6") (pinfunction "20/A6_20/A6") (pintype "bidirectional"))
    )
    (net (code "89") (name "RX") (class "Default")
      (node (ref "TXRX") (pin "1") (pinfunction "1_1") (pintype "passive"))
      (node (ref "U7") (pin "30") (pinfunction "PD0(RXD)_30") (pintype "bidirectional"))
    )
    (net (code "90") (name "SERVO") (class "Default")
      (node (ref "SERVO") (pin "3") (pinfunction "3_3") (pintype "passive"))
      (node (ref "U$1") (pin "9/CS") (pinfunction "9/CS_9/CS") (pintype "bidirectional"))
    )
    (net (code "91") (name "SPI_MISO") (class "Default")
      (node (ref "U$1") (pin "11/MOSI") (pinfunction "11/MOSI_11/MOSI") (pintype "bidirectional"))
      (node (ref "U7") (pin "16") (pinfunction "PB4(MISO)_16") (pintype "bidirectional"))
    )
    (net (code "92") (name "SPI_MOSI") (class "Default")
      (node (ref "U$1") (pin "12/MISO") (pinfunction "12/MISO_12/MISO") (pintype "bidirectional"))
      (node (ref "U7") (pin "15") (pinfunction "PB3(MOSI/OC2)_15") (pintype "bidirectional"))
    )
    (net (code "93") (name "SPI_SCK") (class "Default")
      (node (ref "U$1") (pin "13/SCK") (pinfunction "13/SCK_13/SCK") (pintype "bidirectional"))
      (node (ref "U7") (pin "17") (pinfunction "PB5(SCK)_17") (pintype "bidirectional"))
    )
    (net (code "94") (name "SPI_SS") (class "Default")
      (node (ref "U$1") (pin "10/CS") (pinfunction "10/CS_10/CS") (pintype "bidirectional"))
      (node (ref "U7") (pin "14") (pinfunction "PB2(SS/OC1B)_14") (pintype "bidirectional"))
    )
    (net (code "95") (name "SW1") (class "Default")
      (node (ref "S1") (pin "1") (pinfunction "1_1") (pintype "passive"))
      (node (ref "U$1") (pin "24") (pinfunction "24_24") (pintype "bidirectional"))
    )
    (net (code "96") (name "SW2") (class "Default")
      (node (ref "S1") (pin "2") (pinfunction "2_2") (pintype "passive"))
      (node (ref "U$1") (pin "25") (pinfunction "25_25") (pintype "bidirectional"))
    )
    (net (code "97") (name "SW3") (class "Default")
      (node (ref "S1") (pin "3") (pinfunction "3_3") (pintype "passive"))
      (node (ref "U$1") (pin "26") (pinfunction "26_26") (pintype "bidirectional"))
    )
    (net (code "98") (name "SW4") (class "Default")
      (node (ref "S1") (pin "4") (pinfunction "4_4") (pintype "passive"))
      (node (ref "U$1") (pin "27") (pinfunction "27_27") (pintype "bidirectional"))
    )
    (net (code "99") (name "SW5") (class "Default")
      (node (ref "U$1") (pin "28") (pinfunction "28_28") (pintype "bidirectional"))
    )
    (net (code "100") (name "TX") (class "Default")
      (node (ref "TXRX") (pin "2") (pinfunction "2_2") (pintype "passive"))
      (node (ref "U7") (pin "31") (pinfunction "PD1(TXD)_31") (pintype "bidirectional"))
    )
    (net (code "101") (name "unconnected-(LED1-PadTHERMAL)") (class "Default")
      (node (ref "LED1") (pin "THERMAL") (pinfunction "THERMAL_THERMAL") (pintype "bidirectional"))
    )
    (net (code "102") (name "unconnected-(LED2-PadTHERMAL)") (class "Default")
      (node (ref "LED2") (pin "THERMAL") (pinfunction "THERMAL_THERMAL") (pintype "bidirectional"))
    )
    (net (code "103") (name "unconnected-(SV1-Pad1)") (class "Default")
      (node (ref "SV1") (pin "1") (pinfunction "1_1") (pintype "passive"))
    )
    (net (code "104") (name "unconnected-(SV1-Pad2)") (class "Default")
      (node (ref "SV1") (pin "2") (pinfunction "2_2") (pintype "passive"))
    )
    (net (code "105") (name "unconnected-(SV3-Pad2)") (class "Default")
      (node (ref "SV3") (pin "2") (pinfunction "2_2") (pintype "passive"))
    )
    (net (code "106") (name "unconnected-(SV3-Pad3)") (class "Default")
      (node (ref "SV3") (pin "3") (pinfunction "3_3") (pintype "passive"))
    )
    (net (code "107") (name "unconnected-(SV4-Pad1)") (class "Default")
      (node (ref "SV4") (pin "1") (pinfunction "1_1") (pintype "passive"))
    )
    (net (code "108") (name "unconnected-(SV4-Pad2)") (class "Default")
      (node (ref "SV4") (pin "2") (pinfunction "2_2") (pintype "passive"))
    )
    (net (code "109") (name "unconnected-(SV4-Pad3)") (class "Default")
      (node (ref "SV4") (pin "3") (pinfunction "3_3") (pintype "passive"))
    )
    (net (code "110") (name "unconnected-(SV4-Pad4)") (class "Default")
      (node (ref "SV4") (pin "4") (pinfunction "4_4") (pintype "passive"))
    )
    (net (code "111") (name "unconnected-(SV7-Pad2)") (class "Default")
      (node (ref "SV7") (pin "2") (pinfunction "2_2") (pintype "passive"))
    )
    (net (code "112") (name "unconnected-(SV7-Pad3)") (class "Default")
      (node (ref "SV7") (pin "3") (pinfunction "3_3") (pintype "passive"))
    )
    (net (code "113") (name "unconnected-(SV8-Pad1)") (class "Default")
      (node (ref "SV8") (pin "1") (pinfunction "1_1") (pintype "passive"))
    )
    (net (code "114") (name "unconnected-(SV8-Pad2)") (class "Default")
      (node (ref "SV8") (pin "2") (pinfunction "2_2") (pintype "passive"))
    )
    (net (code "115") (name "unconnected-(SV8-Pad3)") (class "Default")
      (node (ref "SV8") (pin "3") (pinfunction "3_3") (pintype "passive"))
    )
    (net (code "116") (name "unconnected-(SV8-Pad4)") (class "Default")
      (node (ref "SV8") (pin "4") (pinfunction "4_4") (pintype "passive"))
    )
    (net (code "117") (name "unconnected-(U$1-Pad6)") (class "Default")
      (node (ref "U$1") (pin "6") (pinfunction "6_6") (pintype "bidirectional"))
    )
    (net (code "118") (name "unconnected-(U$1-PadVUSB)") (class "Default")
      (node (ref "U$1") (pin "VUSB") (pinfunction "VUSB_VUSB") (pintype "bidirectional"))
    )
    (net (code "119") (name "unconnected-(U$3-PadP1)") (class "Default")
      (node (ref "U$3") (pin "P1") (pinfunction "P1_P1") (pintype "bidirectional"))
    )
    (net (code "120") (name "unconnected-(U$7-PadP1)") (class "Default")
      (node (ref "U$7") (pin "P1") (pinfunction "P1_P1") (pintype "bidirectional"))
    )
    (net (code "121") (name "unconnected-(U7-AREF-Pad20)") (class "Default")
      (node (ref "U7") (pin "20") (pinfunction "AREF_20") (pintype "bidirectional"))
    )
  )
)
